# io-board-f-4.net
KiCad netlist of a schematic drawn in EAGLE
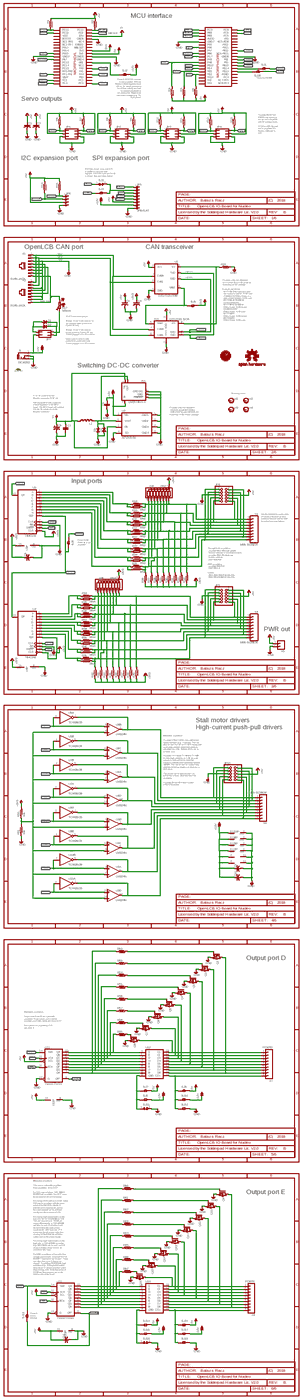
[diagram p0: schematic, sheet 1, overview]
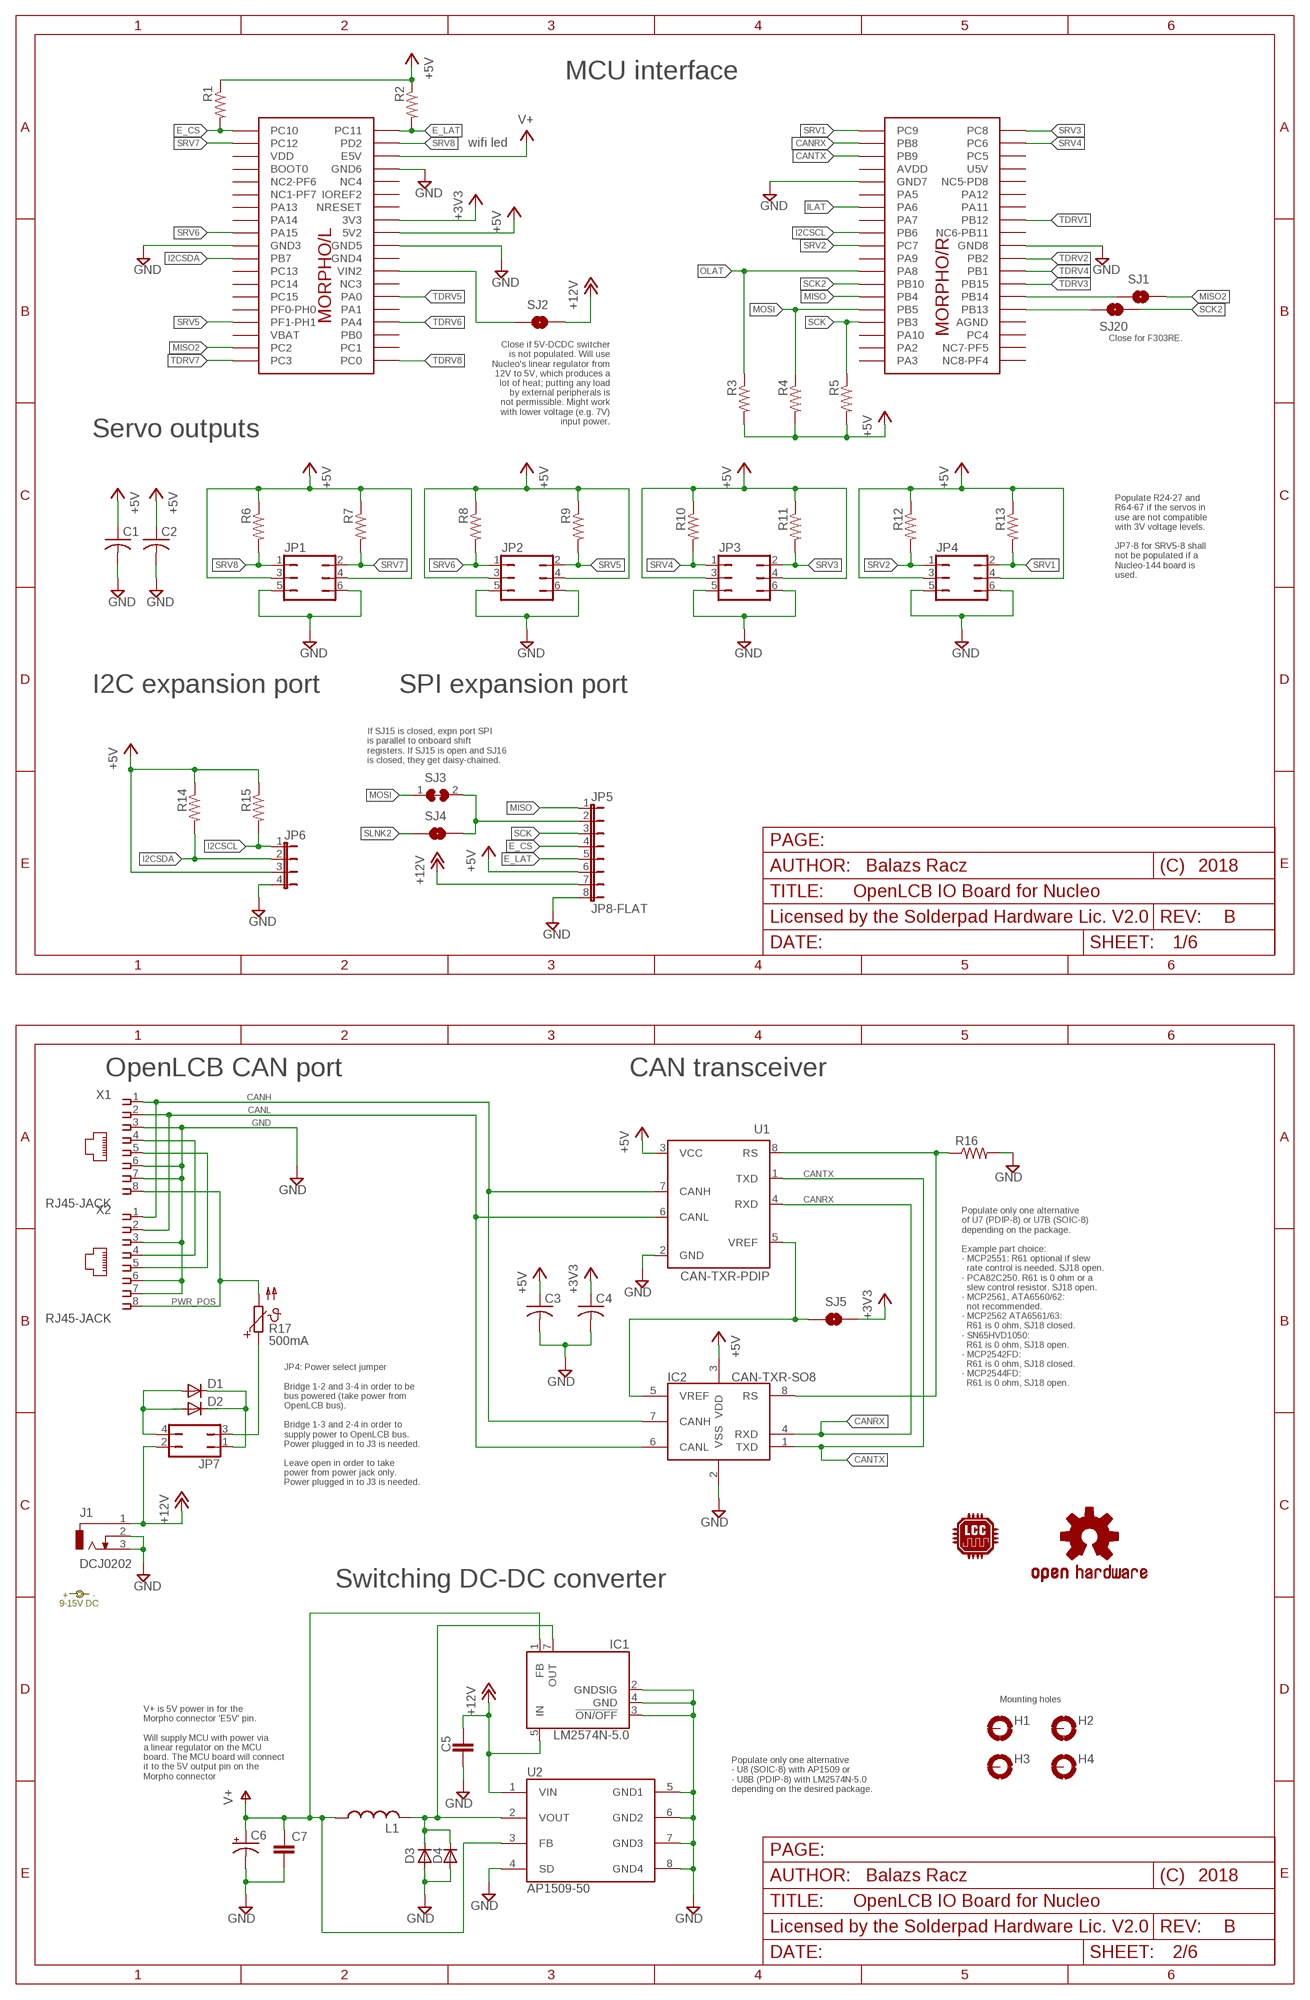
[diagram p1: schematic, sheet 1, part 1 of 4]
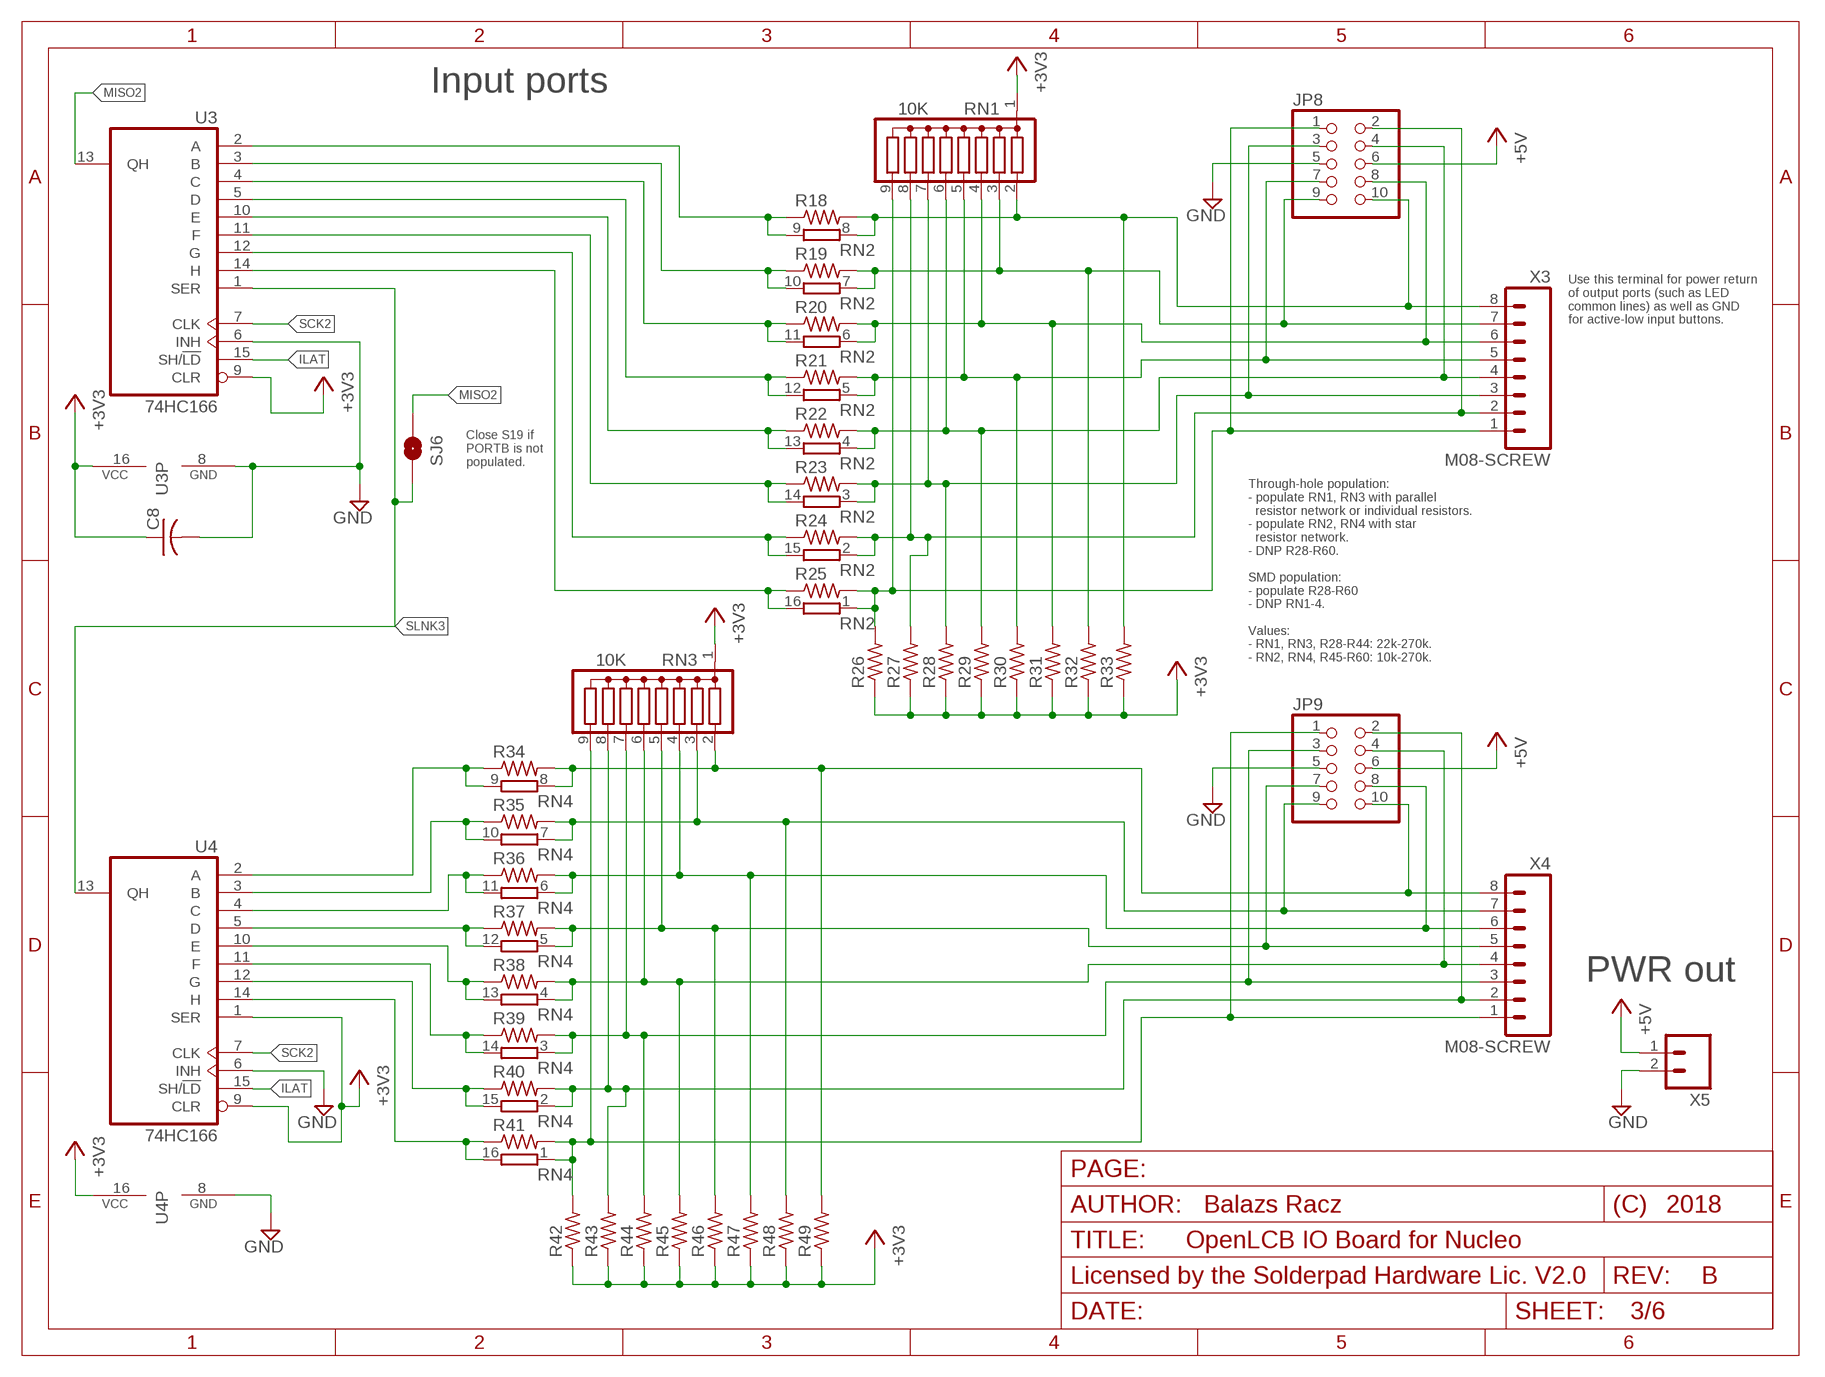
[diagram p2: schematic, sheet 1, part 2 of 4]
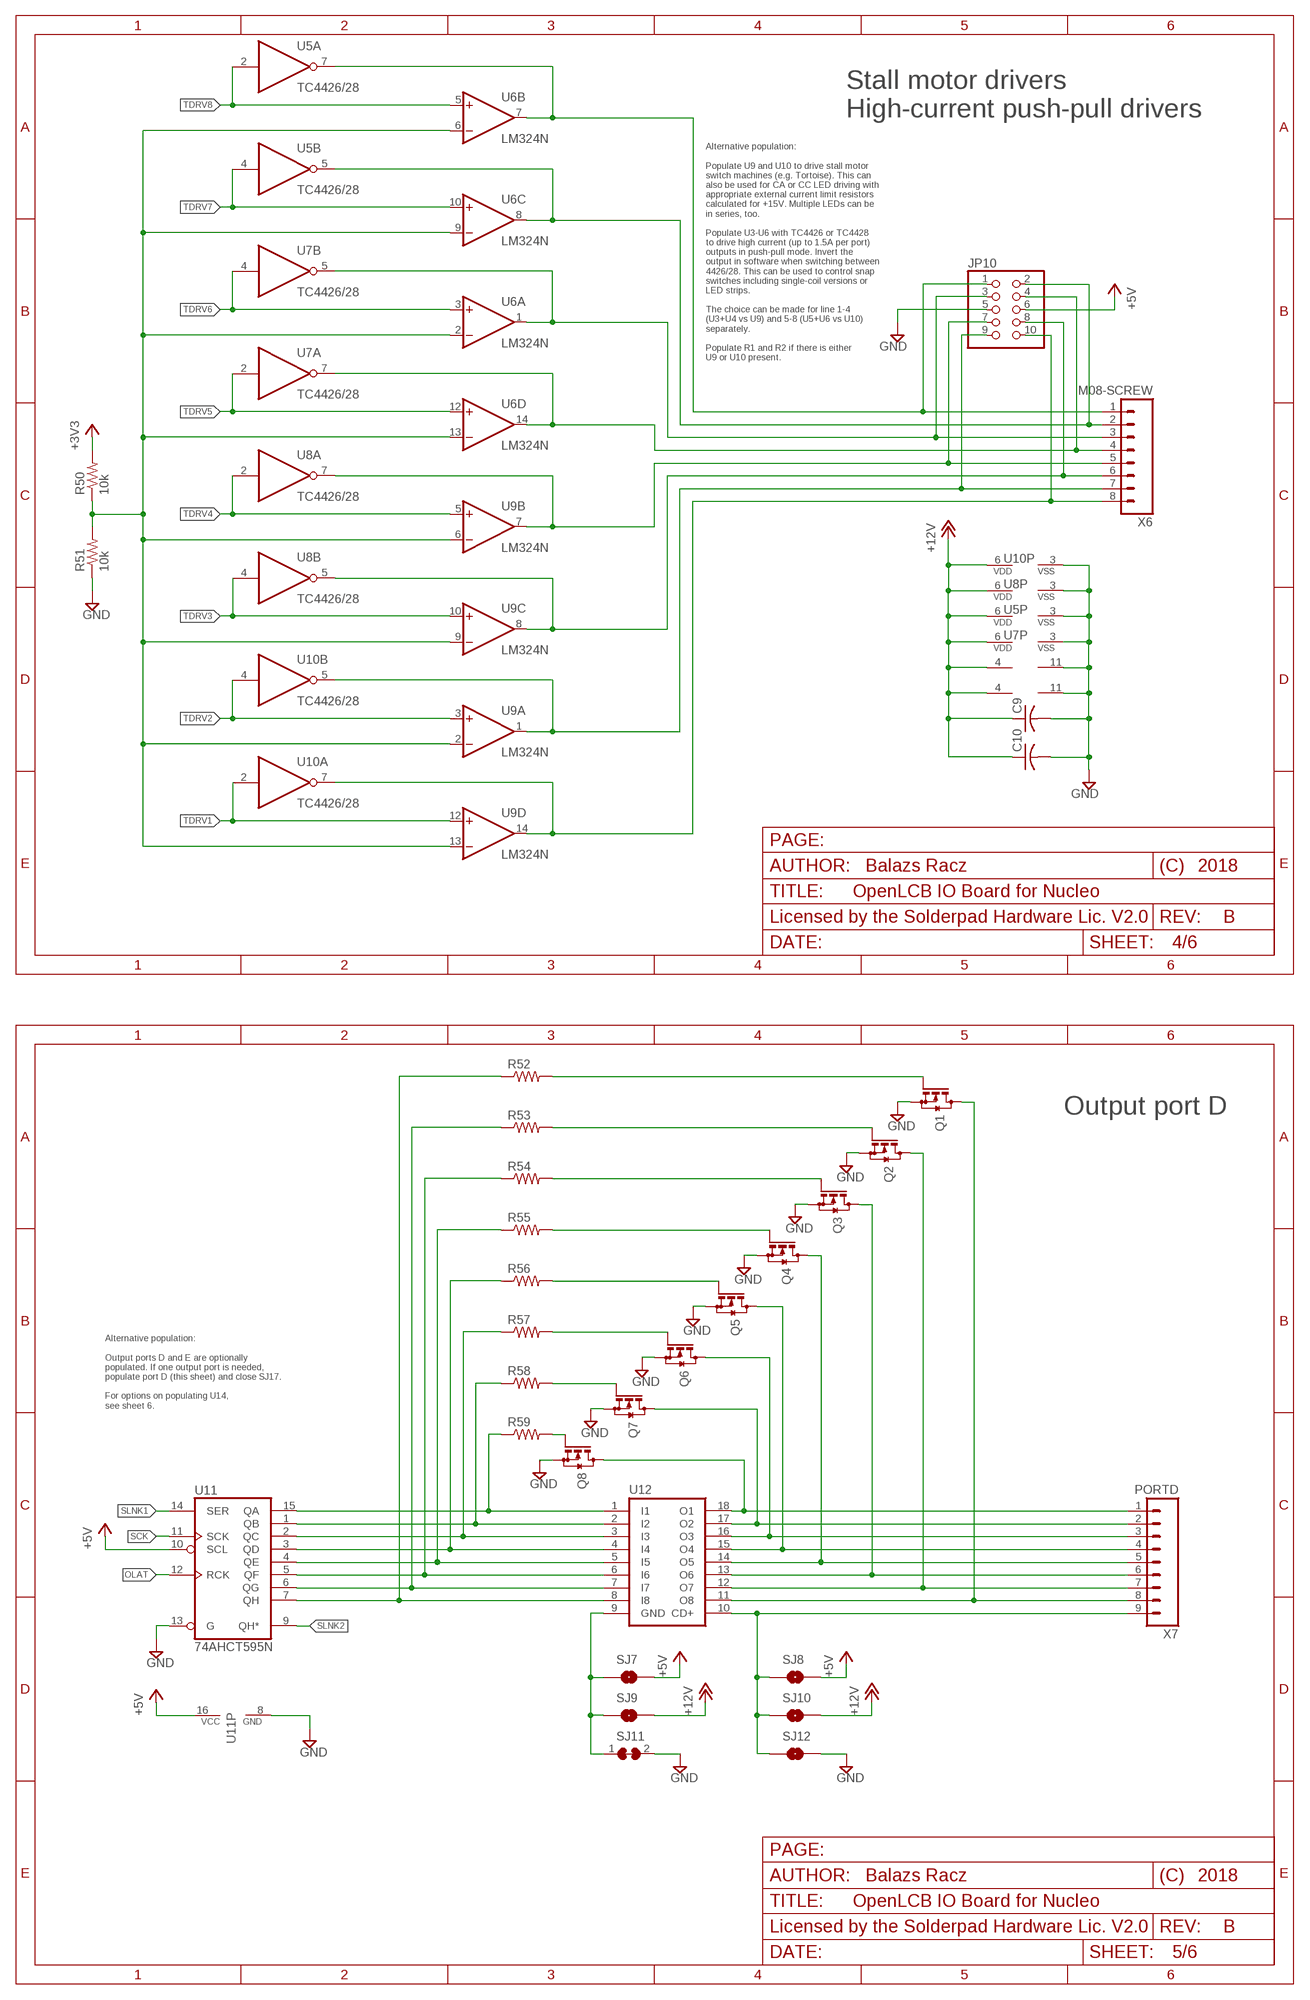
[diagram p3: schematic, sheet 1, part 3 of 4]
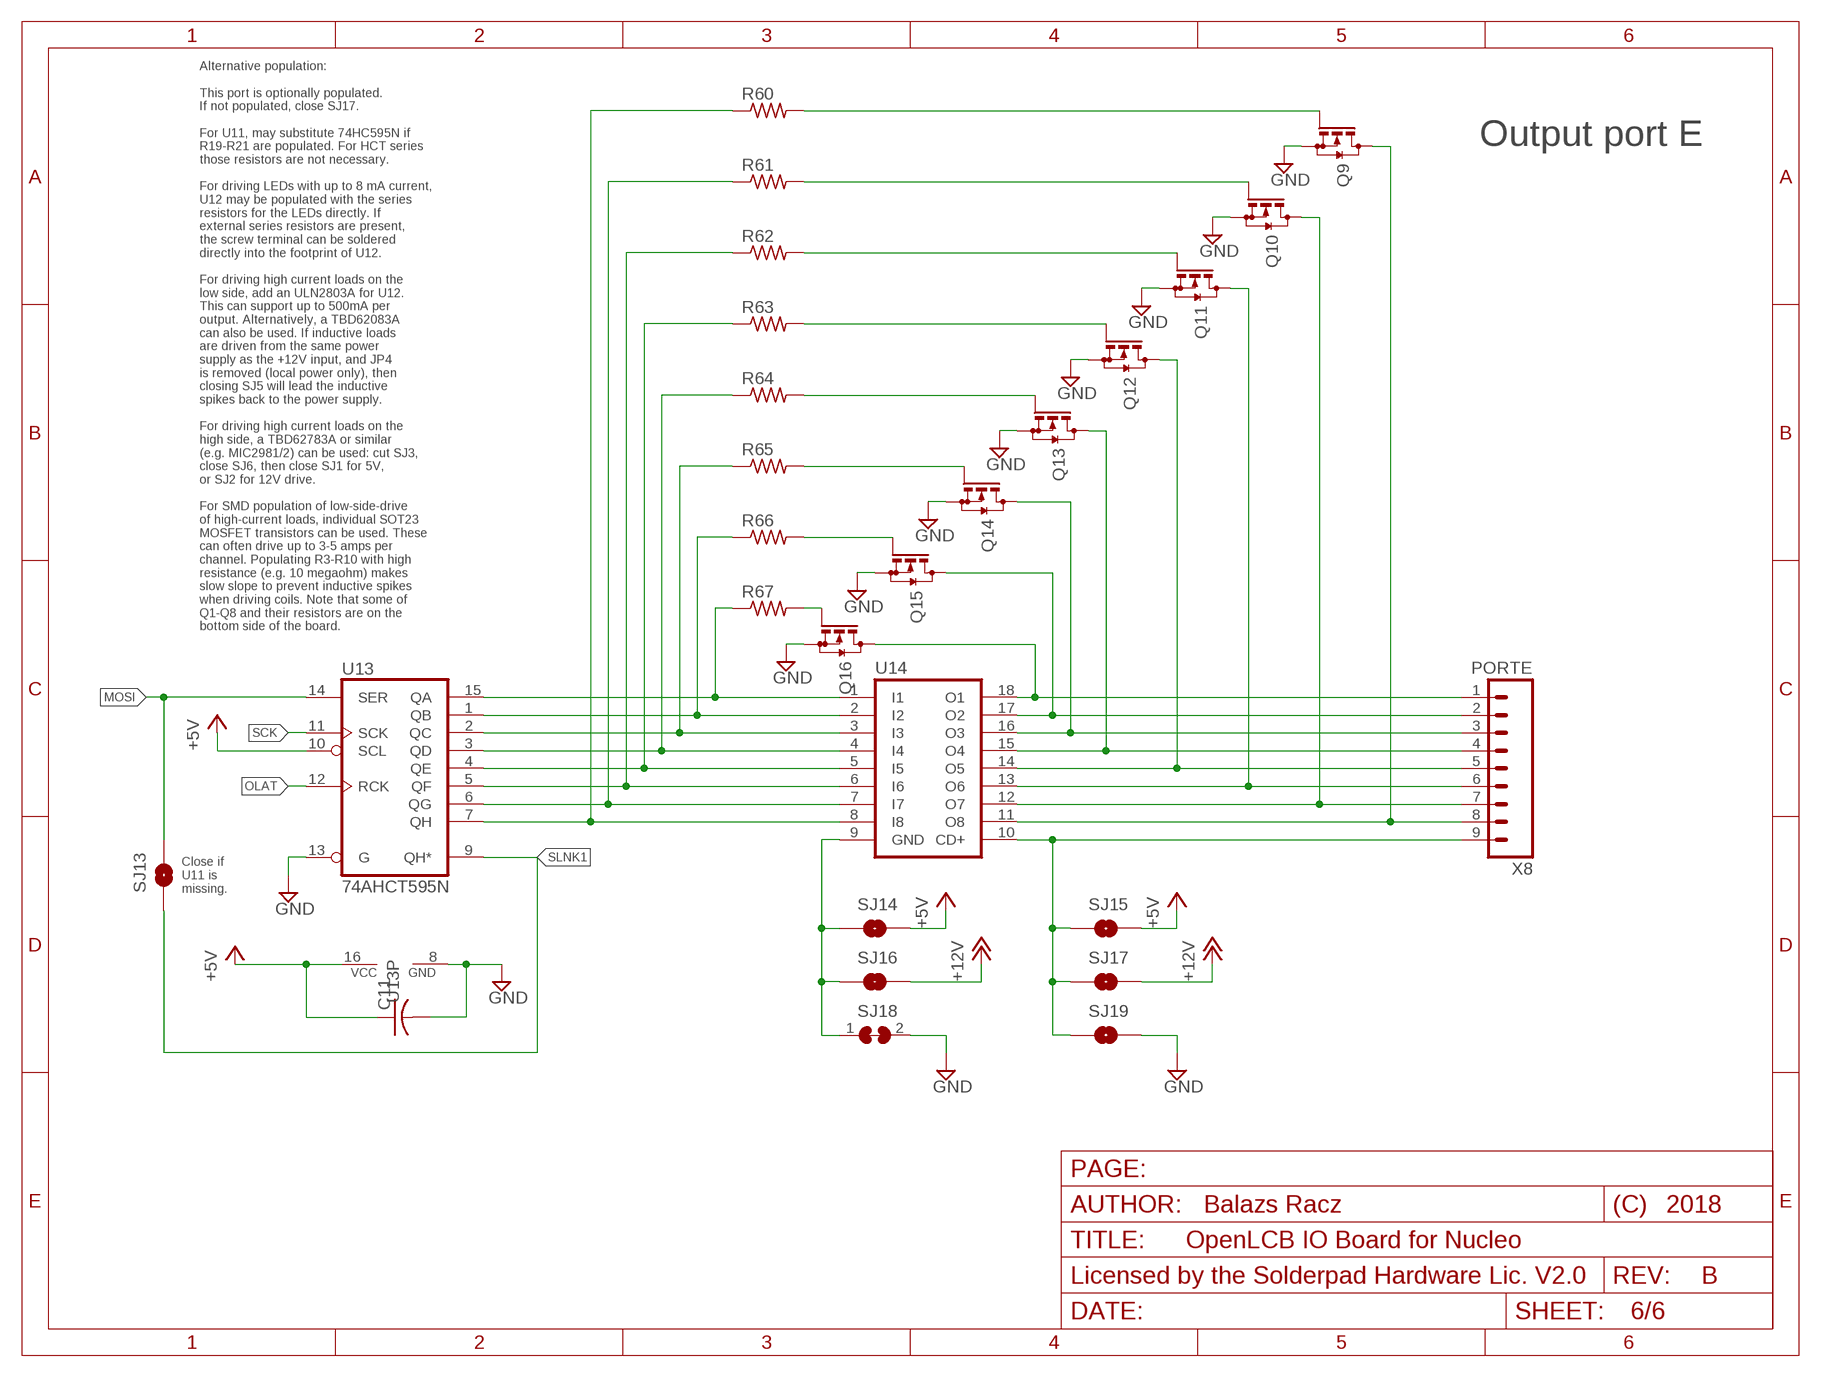
[diagram p4: schematic, sheet 1, part 4 of 4]

(export (version "E")
  (design (tool "Eeschema 10.0.6"))
  (components
    (comp (ref "C1")
      (value "C-USC1206")
      (footprint "eagle-import:C1206")
      (libsource (lib "eagle-import") (part "C-USC1206"))
    )
    (comp (ref "C2")
      (value "C-USC1206")
      (footprint "eagle-import:C1206")
      (libsource (lib "eagle-import") (part "C-USC1206"))
    )
    (comp (ref "C3")
      (value "C-USC0805")
      (footprint "eagle-import:C0805")
      (libsource (lib "eagle-import") (part "C-USC0805"))
    )
    (comp (ref "C4")
      (value "C-USC0805")
      (footprint "eagle-import:C0805")
      (libsource (lib "eagle-import") (part "C-USC0805"))
    )
    (comp (ref "C5")
      (value "C-EUC1206")
      (footprint "eagle-import:C1206")
      (libsource (lib "eagle-import") (part "C-EUC1206"))
    )
    (comp (ref "C6")
      (value "CPOL-USE2.5-5")
      (footprint "eagle-import:E2,5-5")
      (libsource (lib "eagle-import") (part "CPOL-USE2.5-5"))
    )
    (comp (ref "C7")
      (value "C-EUC1206")
      (footprint "eagle-import:C1206")
      (libsource (lib "eagle-import") (part "C-EUC1206"))
    )
    (comp (ref "C8")
      (value "C-USC0805")
      (footprint "eagle-import:C0805")
      (libsource (lib "eagle-import") (part "C-USC0805"))
    )
    (comp (ref "C9")
      (value "C-USC1206")
      (footprint "eagle-import:C1206")
      (libsource (lib "eagle-import") (part "C-USC1206"))
    )
    (comp (ref "C10")
      (value "C-USC1206")
      (footprint "eagle-import:C1206")
      (libsource (lib "eagle-import") (part "C-USC1206"))
    )
    (comp (ref "C11")
      (value "C-USC0805")
      (footprint "eagle-import:C0805")
      (libsource (lib "eagle-import") (part "C-USC0805"))
    )
    (comp (ref "D1")
      (value "DIODEDO-214AA-NODOC")
      (footprint "eagle-import:DO214AA-NODOC")
      (libsource (lib "eagle-import") (part "DIODEDO-214AA-NODOC"))
    )
    (comp (ref "D2")
      (value "DIODE-DO41-7.6")
      (footprint "eagle-import:DO41-7.6")
      (libsource (lib "eagle-import") (part "DIODE-DO41-7.6"))
    )
    (comp (ref "D3")
      (value "DIODE-DO41-7.6")
      (footprint "eagle-import:DO41-7.6")
      (libsource (lib "eagle-import") (part "DIODE-DO41-7.6"))
    )
    (comp (ref "D4")
      (value "DIODEDO-214AA-NODOC")
      (footprint "eagle-import:DO214AA-NODOC")
      (libsource (lib "eagle-import") (part "DIODEDO-214AA-NODOC"))
    )
    (comp (ref "G1")
      (value "NUCLEO_64_GENERIC")
      (footprint "eagle-import:NUCLEO_BRD_BASE64")
      (libsource (lib "eagle-import") (part "NUCLEO_64_GENERIC"))
    )
    (comp (ref "H1")
      (value "MOUNT-PAD-ROUND3.3")
      (footprint "eagle-import:3,3-PAD")
      (libsource (lib "eagle-import") (part "MOUNT-PAD-ROUND3.3"))
    )
    (comp (ref "H2")
      (value "MOUNT-PAD-ROUND3.3")
      (footprint "eagle-import:3,3-PAD")
      (libsource (lib "eagle-import") (part "MOUNT-PAD-ROUND3.3"))
    )
    (comp (ref "H3")
      (value "MOUNT-PAD-ROUND3.3")
      (footprint "eagle-import:3,3-PAD")
      (libsource (lib "eagle-import") (part "MOUNT-PAD-ROUND3.3"))
    )
    (comp (ref "H4")
      (value "MOUNT-PAD-ROUND3.3")
      (footprint "eagle-import:3,3-PAD")
      (libsource (lib "eagle-import") (part "MOUNT-PAD-ROUND3.3"))
    )
    (comp (ref "IC1")
      (value "LM2574N-5.0")
      (footprint "eagle-import:DIL08")
      (libsource (lib "eagle-import") (part "LM2574?-N5.0"))
    )
    (comp (ref "IC2")
      (value "CAN-TXR-SO8")
      (footprint "eagle-import:SO-08")
      (libsource (lib "eagle-import") (part "MCP2551-SN"))
    )
    (comp (ref "J1")
      (value "DCJ0202")
      (footprint "eagle-import:DCJ0202")
      (libsource (lib "eagle-import") (part "DCJ0202"))
    )
    (comp (ref "JP1")
      (value "JP3Q")
      (footprint "eagle-import:JP3Q")
      (libsource (lib "eagle-import") (part "JP3Q"))
    )
    (comp (ref "JP2")
      (value "JP3Q")
      (footprint "eagle-import:JP3Q")
      (libsource (lib "eagle-import") (part "JP3Q"))
    )
    (comp (ref "JP3")
      (value "JP3Q")
      (footprint "eagle-import:JP3Q")
      (libsource (lib "eagle-import") (part "JP3Q"))
    )
    (comp (ref "JP4")
      (value "JP3Q")
      (footprint "eagle-import:JP3Q")
      (libsource (lib "eagle-import") (part "JP3Q"))
    )
    (comp (ref "JP5")
      (value "JP8-FLAT")
      (footprint "eagle-import:JP8F")
      (libsource (lib "eagle-import") (part "JP8-FLAT"))
    )
    (comp (ref "JP6")
      (value "JP4-FLAT")
      (footprint "eagle-import:JP4F")
      (libsource (lib "eagle-import") (part "JP4-FLAT"))
    )
    (comp (ref "JP7")
      (value "JP2Q")
      (footprint "eagle-import:JP2Q")
      (libsource (lib "eagle-import") (part "JP2Q"))
    )
    (comp (ref "JP8")
      (value "PINHD-2X5CN")
      (footprint "eagle-import:CON10M")
      (libsource (lib "eagle-import") (part "PINHD-2X5CN"))
    )
    (comp (ref "JP9")
      (value "PINHD-2X5CN")
      (footprint "eagle-import:CON10M")
      (libsource (lib "eagle-import") (part "PINHD-2X5CN"))
    )
    (comp (ref "JP10")
      (value "PINHD-2X5CN")
      (footprint "eagle-import:CON10M")
      (libsource (lib "eagle-import") (part "PINHD-2X5CN"))
    )
    (comp (ref "L1")
      (value "L-US")
      (footprint "eagle-import:L5-8,5")
      (libsource (lib "eagle-import") (part "L-US"))
    )
    (comp (ref "LG1")
      (value "LCC_LOGO")
      (footprint "eagle-import:LCC_LOGO")
      (libsource (lib "eagle-import") (part "LCC_LOGO"))
    )
    (comp (ref "LOGO1")
      (value "DOC-OSHW-LOGOM")
      (footprint "eagle-import:OSHW-LOGO-M")
      (libsource (lib "eagle-import") (part "DOC-OSHW-LOGOM"))
    )
    (comp (ref "P1")
      (value "9-15V DC")
      (footprint "eagle-import:POWER_USAGE")
      (libsource (lib "eagle-import") (part "DOC-POWER_LABEL"))
    )
    (comp (ref "Q1")
      (value "BSS123")
      (footprint "eagle-import:SOT23")
      (libsource (lib "eagle-import") (part "BSS123"))
    )
    (comp (ref "Q2")
      (value "BSS123")
      (footprint "eagle-import:SOT23")
      (libsource (lib "eagle-import") (part "BSS123"))
    )
    (comp (ref "Q3")
      (value "BSS123")
      (footprint "eagle-import:SOT23")
      (libsource (lib "eagle-import") (part "BSS123"))
    )
    (comp (ref "Q4")
      (value "BSS123")
      (footprint "eagle-import:SOT23")
      (libsource (lib "eagle-import") (part "BSS123"))
    )
    (comp (ref "Q5")
      (value "BSS123")
      (footprint "eagle-import:SOT23")
      (libsource (lib "eagle-import") (part "BSS123"))
    )
    (comp (ref "Q6")
      (value "BSS123")
      (footprint "eagle-import:SOT23")
      (libsource (lib "eagle-import") (part "BSS123"))
    )
    (comp (ref "Q7")
      (value "BSS123")
      (footprint "eagle-import:SOT23")
      (libsource (lib "eagle-import") (part "BSS123"))
    )
    (comp (ref "Q8")
      (value "BSS123")
      (footprint "eagle-import:SOT23")
      (libsource (lib "eagle-import") (part "BSS123"))
    )
    (comp (ref "Q9")
      (value "BSS123")
      (footprint "eagle-import:SOT23")
      (libsource (lib "eagle-import") (part "BSS123"))
    )
    (comp (ref "Q10")
      (value "BSS123")
      (footprint "eagle-import:SOT23")
      (libsource (lib "eagle-import") (part "BSS123"))
    )
    (comp (ref "Q11")
      (value "BSS123")
      (footprint "eagle-import:SOT23")
      (libsource (lib "eagle-import") (part "BSS123"))
    )
    (comp (ref "Q12")
      (value "BSS123")
      (footprint "eagle-import:SOT23")
      (libsource (lib "eagle-import") (part "BSS123"))
    )
    (comp (ref "Q13")
      (value "BSS123")
      (footprint "eagle-import:SOT23")
      (libsource (lib "eagle-import") (part "BSS123"))
    )
    (comp (ref "Q14")
      (value "BSS123")
      (footprint "eagle-import:SOT23")
      (libsource (lib "eagle-import") (part "BSS123"))
    )
    (comp (ref "Q15")
      (value "BSS123")
      (footprint "eagle-import:SOT23")
      (libsource (lib "eagle-import") (part "BSS123"))
    )
    (comp (ref "Q16")
      (value "BSS123")
      (footprint "eagle-import:SOT23")
      (libsource (lib "eagle-import") (part "BSS123"))
    )
    (comp (ref "R1")
      (value "R-US_R0805")
      (footprint "eagle-import:R0805")
      (libsource (lib "eagle-import") (part "rcl_334_R-US_R0805"))
    )
    (comp (ref "R2")
      (value "R-US_R0805")
      (footprint "eagle-import:R0805")
      (libsource (lib "eagle-import") (part "rcl_334_R-US_R0805"))
    )
    (comp (ref "R3")
      (value "R-US_R0805")
      (footprint "eagle-import:R0805")
      (libsource (lib "eagle-import") (part "rcl_334_R-US_R0805"))
    )
    (comp (ref "R4")
      (value "R-US_R0805")
      (footprint "eagle-import:R0805")
      (libsource (lib "eagle-import") (part "rcl_334_R-US_R0805"))
    )
    (comp (ref "R5")
      (value "R-US_R0805")
      (footprint "eagle-import:R0805")
      (libsource (lib "eagle-import") (part "rcl_334_R-US_R0805"))
    )
    (comp (ref "R6")
      (value "R-US_R0805")
      (footprint "eagle-import:R0805")
      (libsource (lib "eagle-import") (part "rcl_334_R-US_R0805"))
    )
    (comp (ref "R7")
      (value "R-US_R0805")
      (footprint "eagle-import:R0805")
      (libsource (lib "eagle-import") (part "rcl_334_R-US_R0805"))
    )
    (comp (ref "R8")
      (value "R-US_R0805")
      (footprint "eagle-import:R0805")
      (libsource (lib "eagle-import") (part "rcl_334_R-US_R0805"))
    )
    (comp (ref "R9")
      (value "R-US_R0805")
      (footprint "eagle-import:R0805")
      (libsource (lib "eagle-import") (part "rcl_334_R-US_R0805"))
    )
    (comp (ref "R10")
      (value "R-US_R0805")
      (footprint "eagle-import:R0805")
      (libsource (lib "eagle-import") (part "rcl_334_R-US_R0805"))
    )
    (comp (ref "R11")
      (value "R-US_R0805")
      (footprint "eagle-import:R0805")
      (libsource (lib "eagle-import") (part "rcl_334_R-US_R0805"))
    )
    (comp (ref "R12")
      (value "R-US_R0805")
      (footprint "eagle-import:R0805")
      (libsource (lib "eagle-import") (part "rcl_334_R-US_R0805"))
    )
    (comp (ref "R13")
      (value "R-US_R0805")
      (footprint "eagle-import:R0805")
      (libsource (lib "eagle-import") (part "rcl_334_R-US_R0805"))
    )
    (comp (ref "R14")
      (value "R-US_R0805")
      (footprint "eagle-import:R0805")
      (libsource (lib "eagle-import") (part "rcl_334_R-US_R0805"))
    )
    (comp (ref "R15")
      (value "R-US_R0805")
      (footprint "eagle-import:R0805")
      (libsource (lib "eagle-import") (part "rcl_334_R-US_R0805"))
    )
    (comp (ref "R16")
      (value "R-US_R0805")
      (footprint "eagle-import:R0805")
      (libsource (lib "eagle-import") (part "rcl_334_R-US_R0805"))
    )
    (comp (ref "R17")
      (value "500mA")
      (footprint "eagle-import:PTC1812")
      (libsource (lib "eagle-import") (part "PTC_1812"))
    )
    (comp (ref "R18")
      (value "R-US_R0603")
      (footprint "eagle-import:R0603")
      (libsource (lib "eagle-import") (part "rcl_334_R-US_R0603"))
    )
    (comp (ref "R19")
      (value "R-US_R0603")
      (footprint "eagle-import:R0603")
      (libsource (lib "eagle-import") (part "rcl_334_R-US_R0603"))
    )
    (comp (ref "R20")
      (value "R-US_R0603")
      (footprint "eagle-import:R0603")
      (libsource (lib "eagle-import") (part "rcl_334_R-US_R0603"))
    )
    (comp (ref "R21")
      (value "R-US_R0603")
      (footprint "eagle-import:R0603")
      (libsource (lib "eagle-import") (part "rcl_334_R-US_R0603"))
    )
    (comp (ref "R22")
      (value "R-US_R0603")
      (footprint "eagle-import:R0603")
      (libsource (lib "eagle-import") (part "rcl_334_R-US_R0603"))
    )
    (comp (ref "R23")
      (value "R-US_R0603")
      (footprint "eagle-import:R0603")
      (libsource (lib "eagle-import") (part "rcl_334_R-US_R0603"))
    )
    (comp (ref "R24")
      (value "R-US_R0603")
      (footprint "eagle-import:R0603")
      (libsource (lib "eagle-import") (part "rcl_334_R-US_R0603"))
    )
    (comp (ref "R25")
      (value "R-US_R0603")
      (footprint "eagle-import:R0603")
      (libsource (lib "eagle-import") (part "rcl_334_R-US_R0603"))
    )
    (comp (ref "R26")
      (value "R-US")
      (footprint "eagle-import:R0603")
      (libsource (lib "eagle-import") (part "R-US"))
    )
    (comp (ref "R27")
      (value "R-US")
      (footprint "eagle-import:R0603")
      (libsource (lib "eagle-import") (part "R-US"))
    )
    (comp (ref "R28")
      (value "R-US")
      (footprint "eagle-import:R0603")
      (libsource (lib "eagle-import") (part "R-US"))
    )
    (comp (ref "R29")
      (value "R-US")
      (footprint "eagle-import:R0603")
      (libsource (lib "eagle-import") (part "R-US"))
    )
    (comp (ref "R30")
      (value "R-US")
      (footprint "eagle-import:R0603")
      (libsource (lib "eagle-import") (part "R-US"))
    )
    (comp (ref "R31")
      (value "R-US")
      (footprint "eagle-import:R0603")
      (libsource (lib "eagle-import") (part "R-US"))
    )
    (comp (ref "R32")
      (value "R-US")
      (footprint "eagle-import:R0603")
      (libsource (lib "eagle-import") (part "R-US"))
    )
    (comp (ref "R33")
      (value "R-US")
      (footprint "eagle-import:R0603")
      (libsource (lib "eagle-import") (part "R-US"))
    )
    (comp (ref "R34")
      (value "R-US_R0603")
      (footprint "eagle-import:R0603")
      (libsource (lib "eagle-import") (part "rcl_334_R-US_R0603"))
    )
    (comp (ref "R35")
      (value "R-US_R0603")
      (footprint "eagle-import:R0603")
      (libsource (lib "eagle-import") (part "rcl_334_R-US_R0603"))
    )
    (comp (ref "R36")
      (value "R-US_R0603")
      (footprint "eagle-import:R0603")
      (libsource (lib "eagle-import") (part "rcl_334_R-US_R0603"))
    )
    (comp (ref "R37")
      (value "R-US_R0603")
      (footprint "eagle-import:R0603")
      (libsource (lib "eagle-import") (part "rcl_334_R-US_R0603"))
    )
    (comp (ref "R38")
      (value "R-US_R0603")
      (footprint "eagle-import:R0603")
      (libsource (lib "eagle-import") (part "rcl_334_R-US_R0603"))
    )
    (comp (ref "R39")
      (value "R-US_R0603")
      (footprint "eagle-import:R0603")
      (libsource (lib "eagle-import") (part "rcl_334_R-US_R0603"))
    )
    (comp (ref "R40")
      (value "R-US_R0603")
      (footprint "eagle-import:R0603")
      (libsource (lib "eagle-import") (part "rcl_334_R-US_R0603"))
    )
    (comp (ref "R41")
      (value "R-US_R0603")
      (footprint "eagle-import:R0603")
      (libsource (lib "eagle-import") (part "rcl_334_R-US_R0603"))
    )
    (comp (ref "R42")
      (value "R-US")
      (footprint "eagle-import:R0603")
      (libsource (lib "eagle-import") (part "R-US"))
    )
    (comp (ref "R43")
      (value "R-US")
      (footprint "eagle-import:R0603")
      (libsource (lib "eagle-import") (part "R-US"))
    )
    (comp (ref "R44")
      (value "R-US")
      (footprint "eagle-import:R0603")
      (libsource (lib "eagle-import") (part "R-US"))
    )
    (comp (ref "R45")
      (value "R-US")
      (footprint "eagle-import:R0603")
      (libsource (lib "eagle-import") (part "R-US"))
    )
    (comp (ref "R46")
      (value "R-US")
      (footprint "eagle-import:R0603")
      (libsource (lib "eagle-import") (part "R-US"))
    )
    (comp (ref "R47")
      (value "R-US")
      (footprint "eagle-import:R0603")
      (libsource (lib "eagle-import") (part "R-US"))
    )
    (comp (ref "R48")
      (value "R-US")
      (footprint "eagle-import:R0603")
      (libsource (lib "eagle-import") (part "R-US"))
    )
    (comp (ref "R49")
      (value "R-US")
      (footprint "eagle-import:R0603")
      (libsource (lib "eagle-import") (part "R-US"))
    )
    (comp (ref "R50")
      (value "10k")
      (footprint "eagle-import:R0805")
      (libsource (lib "eagle-import") (part "R-US_R0805"))
    )
    (comp (ref "R51")
      (value "10k")
      (footprint "eagle-import:R0805")
      (libsource (lib "eagle-import") (part "R-US_R0805"))
    )
    (comp (ref "R52")
      (value "R-US_R0603")
      (footprint "eagle-import:R0603")
      (libsource (lib "eagle-import") (part "R-US_R0603"))
    )
    (comp (ref "R53")
      (value "R-US_R0603")
      (footprint "eagle-import:R0603")
      (libsource (lib "eagle-import") (part "R-US_R0603"))
    )
    (comp (ref "R54")
      (value "R-US_R0603")
      (footprint "eagle-import:R0603")
      (libsource (lib "eagle-import") (part "R-US_R0603"))
    )
    (comp (ref "R55")
      (value "R-US_R0603")
      (footprint "eagle-import:R0603")
      (libsource (lib "eagle-import") (part "R-US_R0603"))
    )
    (comp (ref "R56")
      (value "R-US_R0603")
      (footprint "eagle-import:R0603")
      (libsource (lib "eagle-import") (part "R-US_R0603"))
    )
    (comp (ref "R57")
      (value "R-US_R0603")
      (footprint "eagle-import:R0603")
      (libsource (lib "eagle-import") (part "R-US_R0603"))
    )
    (comp (ref "R58")
      (value "R-US_R0603")
      (footprint "eagle-import:R0603")
      (libsource (lib "eagle-import") (part "R-US_R0603"))
    )
    (comp (ref "R59")
      (value "R-US_R0603")
      (footprint "eagle-import:R0603")
      (libsource (lib "eagle-import") (part "R-US_R0603"))
    )
    (comp (ref "R60")
      (value "R-US_R0603")
      (footprint "eagle-import:R0603")
      (libsource (lib "eagle-import") (part "R-US_R0603"))
    )
    (comp (ref "R61")
      (value "R-US_R0603")
      (footprint "eagle-import:R0603")
      (libsource (lib "eagle-import") (part "R-US_R0603"))
    )
    (comp (ref "R62")
      (value "R-US_R0603")
      (footprint "eagle-import:R0603")
      (libsource (lib "eagle-import") (part "R-US_R0603"))
    )
    (comp (ref "R63")
      (value "R-US_R0603")
      (footprint "eagle-import:R0603")
      (libsource (lib "eagle-import") (part "R-US_R0603"))
    )
    (comp (ref "R64")
      (value "R-US_R0603")
      (footprint "eagle-import:R0603")
      (libsource (lib "eagle-import") (part "R-US_R0603"))
    )
    (comp (ref "R65")
      (value "R-US_R0603")
      (footprint "eagle-import:R0603")
      (libsource (lib "eagle-import") (part "R-US_R0603"))
    )
    (comp (ref "R66")
      (value "R-US_R0603")
      (footprint "eagle-import:R0603")
      (libsource (lib "eagle-import") (part "R-US_R0603"))
    )
    (comp (ref "R67")
      (value "R-US_R0603")
      (footprint "eagle-import:R0603")
      (libsource (lib "eagle-import") (part "R-US_R0603"))
    )
    (comp (ref "RN1")
      (value "10K")
      (footprint "eagle-import:SIL9")
      (libsource (lib "eagle-import") (part "G08R"))
    )
    (comp (ref "RN2")
      (value "8R-P")
      (footprint "eagle-import:DIL16")
      (libsource (lib "eagle-import") (part "8R-P"))
    )
    (comp (ref "RN3")
      (value "10K")
      (footprint "eagle-import:SIL9")
      (libsource (lib "eagle-import") (part "G08R"))
    )
    (comp (ref "RN4")
      (value "8R-P")
      (footprint "eagle-import:DIL16")
      (libsource (lib "eagle-import") (part "8R-P"))
    )
    (comp (ref "SJ1")
      (value "SJRND2")
      (footprint "eagle-import:SJ_RND2")
      (libsource (lib "eagle-import") (part "SJRND2"))
    )
    (comp (ref "SJ2")
      (value "SJRND2")
      (footprint "eagle-import:SJ_RND2")
      (libsource (lib "eagle-import") (part "SJRND2"))
    )
    (comp (ref "SJ3")
      (value "SJ-C")
      (footprint "eagle-import:SJW-C")
      (libsource (lib "eagle-import") (part "SJ-C"))
    )
    (comp (ref "SJ4")
      (value "SJRND2")
      (footprint "eagle-import:SJ_RND2")
      (libsource (lib "eagle-import") (part "SJRND2"))
    )
    (comp (ref "SJ5")
      (value "SJRND2")
      (footprint "eagle-import:SJ_RND2")
      (libsource (lib "eagle-import") (part "SJRND2"))
    )
    (comp (ref "SJ6")
      (value "SJRND2")
      (footprint "eagle-import:SJ_RND2")
      (libsource (lib "eagle-import") (part "SJRND2"))
    )
    (comp (ref "SJ7")
      (value "SJRND2")
      (footprint "eagle-import:SJ_RND2")
      (libsource (lib "eagle-import") (part "SJRND2"))
    )
    (comp (ref "SJ8")
      (value "SJRND2")
      (footprint "eagle-import:SJ_RND2")
      (libsource (lib "eagle-import") (part "SJRND2"))
    )
    (comp (ref "SJ9")
      (value "SJRND2")
      (footprint "eagle-import:SJ_RND2")
      (libsource (lib "eagle-import") (part "SJRND2"))
    )
    (comp (ref "SJ10")
      (value "SJRND2")
      (footprint "eagle-import:SJ_RND2")
      (libsource (lib "eagle-import") (part "SJRND2"))
    )
    (comp (ref "SJ11")
      (value "SJ-C")
      (footprint "eagle-import:SJW-C")
      (libsource (lib "eagle-import") (part "SJ-C"))
    )
    (comp (ref "SJ12")
      (value "SJRND2")
      (footprint "eagle-import:SJ_RND2")
      (libsource (lib "eagle-import") (part "SJRND2"))
    )
    (comp (ref "SJ13")
      (value "SJRND2")
      (footprint "eagle-import:SJ_RND2")
      (libsource (lib "eagle-import") (part "SJRND2"))
    )
    (comp (ref "SJ14")
      (value "SJRND2")
      (footprint "eagle-import:SJ_RND2")
      (libsource (lib "eagle-import") (part "SJRND2"))
    )
    (comp (ref "SJ15")
      (value "SJRND2")
      (footprint "eagle-import:SJ_RND2")
      (libsource (lib "eagle-import") (part "SJRND2"))
    )
    (comp (ref "SJ16")
      (value "SJRND2")
      (footprint "eagle-import:SJ_RND2")
      (libsource (lib "eagle-import") (part "SJRND2"))
    )
    (comp (ref "SJ17")
      (value "SJRND2")
      (footprint "eagle-import:SJ_RND2")
      (libsource (lib "eagle-import") (part "SJRND2"))
    )
    (comp (ref "SJ18")
      (value "SJ-C")
      (footprint "eagle-import:SJW-C")
      (libsource (lib "eagle-import") (part "SJ-C"))
    )
    (comp (ref "SJ19")
      (value "SJRND2")
      (footprint "eagle-import:SJ_RND2")
      (libsource (lib "eagle-import") (part "SJRND2"))
    )
    (comp (ref "SJ20")
      (value "SJRND2")
      (footprint "eagle-import:SJ_RND2")
      (libsource (lib "eagle-import") (part "SJRND2"))
    )
    (comp (ref "U1")
      (value "CAN-TXR-PDIP")
      (footprint "eagle-import:DIL08")
      (libsource (lib "eagle-import") (part "PCA82C250"))
    )
    (comp (ref "U2")
      (value "AP1509-50")
      (footprint "eagle-import:SO-08")
      (libsource (lib "eagle-import") (part "AP1509"))
    )
    (comp (ref "U3")
      (value "74HC166")
      (footprint "eagle-import:DIL16")
      (libsource (lib "eagle-import") (part "74166N"))
    )
    (comp (ref "U4")
      (value "74HC166")
      (footprint "eagle-import:DIL16")
      (libsource (lib "eagle-import") (part "74166N"))
    )
    (comp (ref "U5")
      (value "TC4426/28")
      (footprint "eagle-import:DIL08-LONG")
      (libsource (lib "eagle-import") (part "TC4426APDIP"))
    )
    (comp (ref "U6")
      (value "LM324N")
      (footprint "eagle-import:DIL14")
      (libsource (lib "eagle-import") (part "LM324N"))
    )
    (comp (ref "U7")
      (value "TC4426/28")
      (footprint "eagle-import:DIL08-LONG")
      (libsource (lib "eagle-import") (part "TC4426APDIP"))
    )
    (comp (ref "U8")
      (value "TC4426/28")
      (footprint "eagle-import:DIL08-LONG")
      (libsource (lib "eagle-import") (part "TC4426APDIP"))
    )
    (comp (ref "U9")
      (value "LM324N")
      (footprint "eagle-import:DIL14")
      (libsource (lib "eagle-import") (part "LM324N"))
    )
    (comp (ref "U10")
      (value "TC4426/28")
      (footprint "eagle-import:DIL08-LONG")
      (libsource (lib "eagle-import") (part "TC4426APDIP"))
    )
    (comp (ref "U11")
      (value "74AHCT595N")
      (footprint "eagle-import:DIL16")
      (libsource (lib "eagle-import") (part "74595NHCT"))
    )
    (comp (ref "U12")
      (value "ULN2803A")
      (footprint "eagle-import:DIL18-THIN")
      (libsource (lib "eagle-import") (part "ULN2803A"))
    )
    (comp (ref "U13")
      (value "74AHCT595N")
      (footprint "eagle-import:DIL16")
      (libsource (lib "eagle-import") (part "74595NHCT"))
    )
    (comp (ref "U14")
      (value "ULN2803A")
      (footprint "eagle-import:DIL18-THIN")
      (libsource (lib "eagle-import") (part "ULN2803A"))
    )
    (comp (ref "X1")
      (value "RJ45-JACK")
      (footprint "eagle-import:RJ45-PULSE-E5J88")
      (libsource (lib "eagle-import") (part "RJ45-JACKRJ45-PULSE-E5J00"))
    )
    (comp (ref "X2")
      (value "RJ45-JACK")
      (footprint "eagle-import:RJ45-PULSE-E5J88")
      (libsource (lib "eagle-import") (part "RJ45-JACKRJ45-PULSE-E5J00"))
    )
    (comp (ref "X3")
      (value "M08-SCREW")
      (footprint "eagle-import:1X08_TERMINAL")
      (libsource (lib "eagle-import") (part "M08-SCREW"))
    )
    (comp (ref "X4")
      (value "M08-SCREW")
      (footprint "eagle-import:1X08_TERMINAL")
      (libsource (lib "eagle-import") (part "M08-SCREW"))
    )
    (comp (ref "X5")
      (value "CONNECTOR-M023.5MM-LOCK")
      (footprint "eagle-import:SCREWTERMINAL-3.5MM-2_LOCK")
      (libsource (lib "eagle-import") (part "CONNECTOR-M023.5MM-LOCK"))
    )
    (comp (ref "X6")
      (value "M08-SCREW")
      (footprint "eagle-import:1X08_TERMINAL")
      (libsource (lib "eagle-import") (part "M08-SCREW"))
    )
    (comp (ref "X7")
      (value "PORTD")
      (footprint "eagle-import:1X09_TERMINAL")
      (libsource (lib "eagle-import") (part "M09-SCREW"))
    )
    (comp (ref "X8")
      (value "PORTE")
      (footprint "eagle-import:1X09_TERMINAL")
      (libsource (lib "eagle-import") (part "M09-SCREW"))
    )
  )
  (nets
    (net (code "1") (name "+3V3") (class "Default")
      (node (ref "C4") (pin "1") (pinfunction "1_1") (pintype "passive"))
      (node (ref "C8") (pin "1") (pinfunction "1_1") (pintype "passive"))
      (node (ref "G1") (pin "3V3") (pinfunction "3V3_3V3") (pintype "power_in"))
      (node (ref "R26") (pin "1") (pinfunction "1_1") (pintype "passive"))
      (node (ref "R27") (pin "1") (pinfunction "1_1") (pintype "passive"))
      (node (ref "R28") (pin "1") (pinfunction "1_1") (pintype "passive"))
      (node (ref "R29") (pin "1") (pinfunction "1_1") (pintype "passive"))
      (node (ref "R30") (pin "1") (pinfunction "1_1") (pintype "passive"))
      (node (ref "R31") (pin "1") (pinfunction "1_1") (pintype "passive"))
      (node (ref "R32") (pin "1") (pinfunction "1_1") (pintype "passive"))
      (node (ref "R33") (pin "1") (pinfunction "1_1") (pintype "passive"))
      (node (ref "R42") (pin "1") (pinfunction "1_1") (pintype "passive"))
      (node (ref "R43") (pin "1") (pinfunction "1_1") (pintype "passive"))
      (node (ref "R44") (pin "1") (pinfunction "1_1") (pintype "passive"))
      (node (ref "R45") (pin "1") (pinfunction "1_1") (pintype "passive"))
      (node (ref "R46") (pin "1") (pinfunction "1_1") (pintype "passive"))
      (node (ref "R47") (pin "1") (pinfunction "1_1") (pintype "passive"))
      (node (ref "R48") (pin "1") (pinfunction "1_1") (pintype "passive"))
      (node (ref "R49") (pin "1") (pinfunction "1_1") (pintype "passive"))
      (node (ref "R50") (pin "2") (pinfunction "2_2") (pintype "passive"))
      (node (ref "RN1") (pin "1") (pinfunction "1_1") (pintype "passive"))
      (node (ref "RN3") (pin "1") (pinfunction "1_1") (pintype "passive"))
      (node (ref "SJ5") (pin "P$1") (pinfunction "1_P$1") (pintype "passive"))
      (node (ref "U3") (pin "16") (pinfunction "VCC_16") (pintype "power_in"))
      (node (ref "U3") (pin "9") (pinfunction "CLR_9") (pintype "input"))
      (node (ref "U4") (pin "1") (pinfunction "SER_1") (pintype "input"))
      (node (ref "U4") (pin "16") (pinfunction "VCC_16") (pintype "power_in"))
      (node (ref "U4") (pin "9") (pinfunction "CLR_9") (pintype "input"))
    )
    (net (code "2") (name "+5V") (class "Default")
      (node (ref "C1") (pin "1") (pinfunction "1_1") (pintype "passive"))
      (node (ref "C11") (pin "1") (pinfunction "1_1") (pintype "passive"))
      (node (ref "C2") (pin "1") (pinfunction "1_1") (pintype "passive"))
      (node (ref "C3") (pin "1") (pinfunction "1_1") (pintype "passive"))
      (node (ref "G1") (pin "5V2") (pinfunction "5V2_5V2") (pintype "power_in"))
      (node (ref "IC2") (pin "3") (pinfunction "VDD_3") (pintype "power_in"))
      (node (ref "JP1") (pin "3") (pinfunction "3_3") (pintype "passive"))
      (node (ref "JP1") (pin "4") (pinfunction "4_4") (pintype "passive"))
      (node (ref "JP10") (pin "6") (pinfunction "6_6") (pintype "passive"))
      (node (ref "JP2") (pin "3") (pinfunction "3_3") (pintype "passive"))
      (node (ref "JP2") (pin "4") (pinfunction "4_4") (pintype "passive"))
      (node (ref "JP3") (pin "3") (pinfunction "3_3") (pintype "passive"))
      (node (ref "JP3") (pin "4") (pinfunction "4_4") (pintype "passive"))
      (node (ref "JP4") (pin "3") (pinfunction "3_3") (pintype "passive"))
      (node (ref "JP4") (pin "4") (pinfunction "4_4") (pintype "passive"))
      (node (ref "JP5") (pin "6") (pinfunction "6_6") (pintype "passive"))
      (node (ref "JP6") (pin "3") (pinfunction "3_3") (pintype "passive"))
      (node (ref "JP8") (pin "6") (pinfunction "6_6") (pintype "passive"))
      (node (ref "JP9") (pin "6") (pinfunction "6_6") (pintype "passive"))
      (node (ref "R1") (pin "1") (pinfunction "1_1") (pintype "passive"))
      (node (ref "R10") (pin "1") (pinfunction "1_1") (pintype "passive"))
      (node (ref "R11") (pin "1") (pinfunction "1_1") (pintype "passive"))
      (node (ref "R12") (pin "1") (pinfunction "1_1") (pintype "passive"))
      (node (ref "R13") (pin "1") (pinfunction "1_1") (pintype "passive"))
      (node (ref "R14") (pin "1") (pinfunction "1_1") (pintype "passive"))
      (node (ref "R15") (pin "1") (pinfunction "1_1") (pintype "passive"))
      (node (ref "R2") (pin "1") (pinfunction "1_1") (pintype "passive"))
      (node (ref "R3") (pin "2") (pinfunction "2_2") (pintype "passive"))
      (node (ref "R4") (pin "2") (pinfunction "2_2") (pintype "passive"))
      (node (ref "R5") (pin "2") (pinfunction "2_2") (pintype "passive"))
      (node (ref "R6") (pin "1") (pinfunction "1_1") (pintype "passive"))
      (node (ref "R7") (pin "1") (pinfunction "1_1") (pintype "passive"))
      (node (ref "R8") (pin "1") (pinfunction "1_1") (pintype "passive"))
      (node (ref "R9") (pin "1") (pinfunction "1_1") (pintype "passive"))
      (node (ref "SJ14") (pin "P$2") (pinfunction "2_P$2") (pintype "passive"))
      (node (ref "SJ15") (pin "P$2") (pinfunction "2_P$2") (pintype "passive"))
      (node (ref "SJ7") (pin "P$2") (pinfunction "2_P$2") (pintype "passive"))
      (node (ref "SJ8") (pin "P$2") (pinfunction "2_P$2") (pintype "passive"))
      (node (ref "U1") (pin "3") (pinfunction "VCC_3") (pintype "power_in"))
      (node (ref "U11") (pin "10") (pinfunction "SCL_10") (pintype "input"))
      (node (ref "U11") (pin "16") (pinfunction "VCC_16") (pintype "power_in"))
      (node (ref "U13") (pin "10") (pinfunction "SCL_10") (pintype "input"))
      (node (ref "U13") (pin "16") (pinfunction "VCC_16") (pintype "power_in"))
      (node (ref "X5") (pin "1") (pinfunction "1_1") (pintype "passive"))
    )
    (net (code "3") (name "+12V") (class "Default")
      (node (ref "C10") (pin "1") (pinfunction "1_1") (pintype "passive"))
      (node (ref "C5") (pin "1") (pinfunction "1_1") (pintype "passive"))
      (node (ref "C9") (pin "1") (pinfunction "1_1") (pintype "passive"))
      (node (ref "IC1") (pin "5") (pinfunction "IN_5") (pintype "input"))
      (node (ref "J1") (pin "1") (pinfunction "1_1") (pintype "passive"))
      (node (ref "JP5") (pin "7") (pinfunction "7_7") (pintype "passive"))
      (node (ref "JP7") (pin "2") (pinfunction "2_2") (pintype "passive"))
      (node (ref "SJ10") (pin "P$2") (pinfunction "2_P$2") (pintype "passive"))
      (node (ref "SJ16") (pin "P$2") (pinfunction "2_P$2") (pintype "passive"))
      (node (ref "SJ17") (pin "P$2") (pinfunction "2_P$2") (pintype "passive"))
      (node (ref "SJ2") (pin "P$2") (pinfunction "2_P$2") (pintype "passive"))
      (node (ref "SJ9") (pin "P$2") (pinfunction "2_P$2") (pintype "passive"))
      (node (ref "U10") (pin "6") (pinfunction "VDD_6") (pintype "power_in"))
      (node (ref "U2") (pin "1") (pinfunction "VIN_1") (pintype "bidirectional"))
      (node (ref "U5") (pin "6") (pinfunction "VDD_6") (pintype "power_in"))
      (node (ref "U6") (pin "4") (pinfunction "V+_4") (pintype "power_in"))
      (node (ref "U7") (pin "6") (pinfunction "VDD_6") (pintype "power_in"))
      (node (ref "U8") (pin "6") (pinfunction "VDD_6") (pintype "power_in"))
      (node (ref "U9") (pin "4") (pinfunction "V+_4") (pintype "power_in"))
    )
    (net (code "4") (name "/AGND") (class "Default")
      (node (ref "G1") (pin "AGND") (pinfunction "AGND_AGND") (pintype "power_in"))
    )
    (net (code "5") (name "/AVDD") (class "Default")
      (node (ref "G1") (pin "AVDD") (pinfunction "AVDD_AVDD") (pintype "power_in"))
    )
    (net (code "6") (name "/CANH") (class "Default")
      (node (ref "IC2") (pin "7") (pinfunction "CANH_7") (pintype "bidirectional"))
      (node (ref "U1") (pin "7") (pinfunction "CANH_7") (pintype "bidirectional"))
      (node (ref "X1") (pin "1") (pinfunction "1_1") (pintype "passive"))
      (node (ref "X2") (pin "1") (pinfunction "1_1") (pintype "passive"))
    )
    (net (code "7") (name "/CANL") (class "Default")
      (node (ref "IC2") (pin "6") (pinfunction "CANL_6") (pintype "bidirectional"))
      (node (ref "U1") (pin "6") (pinfunction "CANL_6") (pintype "bidirectional"))
      (node (ref "X1") (pin "2") (pinfunction "2_2") (pintype "passive"))
      (node (ref "X2") (pin "2") (pinfunction "2_2") (pintype "passive"))
    )
    (net (code "8") (name "/GND4") (class "Default")
      (node (ref "G1") (pin "GND4") (pinfunction "GND4_GND4") (pintype "power_in"))
    )
    (net (code "9") (name "/PWR_POS") (class "Default")
      (node (ref "R17") (pin "2") (pinfunction "2_2") (pintype "passive"))
      (node (ref "X1") (pin "8") (pinfunction "8_8") (pintype "passive"))
      (node (ref "X2") (pin "8") (pinfunction "8_8") (pintype "passive"))
    )
    (net (code "10") (name "/U5V") (class "Default")
      (node (ref "G1") (pin "U5V") (pinfunction "U5V_U5V") (pintype "power_in"))
    )
    (net (code "11") (name "/VBAT") (class "Default")
      (node (ref "G1") (pin "VBAT") (pinfunction "VBAT_VBAT") (pintype "power_in"))
    )
    (net (code "12") (name "/VDD") (class "Default")
      (node (ref "G1") (pin "VDD") (pinfunction "VDD_VDD") (pintype "power_in"))
    )
    (net (code "13") (name "CANRX") (class "Default")
      (node (ref "G1") (pin "PB8") (pinfunction "PB8_PB8") (pintype "bidirectional"))
      (node (ref "IC2") (pin "4") (pinfunction "RXD_4") (pintype "bidirectional"))
      (node (ref "U1") (pin "4") (pinfunction "RXD_4") (pintype "output"))
    )
    (net (code "14") (name "CANTX") (class "Default")
      (node (ref "G1") (pin "PB9") (pinfunction "PB9_PB9") (pintype "bidirectional"))
      (node (ref "IC2") (pin "1") (pinfunction "TXD_1") (pintype "bidirectional"))
      (node (ref "U1") (pin "1") (pinfunction "TXD_1") (pintype "input"))
    )
    (net (code "15") (name "E_CS") (class "Default")
      (node (ref "G1") (pin "PC10") (pinfunction "PC10_PC10") (pintype "bidirectional"))
      (node (ref "JP5") (pin "4") (pinfunction "4_4") (pintype "passive"))
      (node (ref "R1") (pin "2") (pinfunction "2_2") (pintype "passive"))
    )
    (net (code "16") (name "E_LAT") (class "Default")
      (node (ref "G1") (pin "PC11") (pinfunction "PC11_PC11") (pintype "bidirectional"))
      (node (ref "JP5") (pin "5") (pinfunction "5_5") (pintype "passive"))
      (node (ref "R2") (pin "2") (pinfunction "2_2") (pintype "passive"))
    )
    (net (code "17") (name "GND") (class "Default")
      (node (ref "C1") (pin "2") (pinfunction "2_2") (pintype "passive"))
      (node (ref "C10") (pin "2") (pinfunction "2_2") (pintype "passive"))
      (node (ref "C11") (pin "2") (pinfunction "2_2") (pintype "passive"))
      (node (ref "C2") (pin "2") (pinfunction "2_2") (pintype "passive"))
      (node (ref "C3") (pin "2") (pinfunction "2_2") (pintype "passive"))
      (node (ref "C4") (pin "2") (pinfunction "2_2") (pintype "passive"))
      (node (ref "C5") (pin "2") (pinfunction "2_2") (pintype "passive"))
      (node (ref "C6") (pin "-") (pinfunction "-_-") (pintype "passive"))
      (node (ref "C7") (pin "2") (pinfunction "2_2") (pintype "passive"))
      (node (ref "C8") (pin "2") (pinfunction "2_2") (pintype "passive"))
      (node (ref "C9") (pin "2") (pinfunction "2_2") (pintype "passive"))
      (node (ref "D3") (pin "A") (pinfunction "A_A") (pintype "passive"))
      (node (ref "D4") (pin "A") (pinfunction "A_A") (pintype "passive"))
      (node (ref "G1") (pin "GND3") (pinfunction "GND3_GND3") (pintype "power_in"))
      (node (ref "G1") (pin "GND5") (pinfunction "GND5_GND5") (pintype "power_in"))
      (node (ref "G1") (pin "GND6") (pinfunction "GND6_GND6") (pintype "power_in"))
      (node (ref "G1") (pin "GND7") (pinfunction "GND7_GND7") (pintype "power_in"))
      (node (ref "G1") (pin "GND8") (pinfunction "GND8_GND8") (pintype "power_in"))
      (node (ref "IC1") (pin "2") (pinfunction "GNDSIG_2") (pintype "input"))
      (node (ref "IC1") (pin "3") (pinfunction "~{ON/OFF}_3") (pintype "input"))
      (node (ref "IC1") (pin "4") (pinfunction "GND_4") (pintype "power_in"))
      (node (ref "IC2") (pin "2") (pinfunction "VSS_2") (pintype "power_in"))
      (node (ref "J1") (pin "2") (pinfunction "2_2") (pintype "passive"))
      (node (ref "J1") (pin "3") (pinfunction "3_3") (pintype "passive"))
      (node (ref "JP1") (pin "5") (pinfunction "5_5") (pintype "passive"))
      (node (ref "JP1") (pin "6") (pinfunction "6_6") (pintype "passive"))
      (node (ref "JP10") (pin "5") (pinfunction "5_5") (pintype "passive"))
      (node (ref "JP2") (pin "5") (pinfunction "5_5") (pintype "passive"))
      (node (ref "JP2") (pin "6") (pinfunction "6_6") (pintype "passive"))
      (node (ref "JP3") (pin "5") (pinfunction "5_5") (pintype "passive"))
      (node (ref "JP3") (pin "6") (pinfunction "6_6") (pintype "passive"))
      (node (ref "JP4") (pin "5") (pinfunction "5_5") (pintype "passive"))
      (node (ref "JP4") (pin "6") (pinfunction "6_6") (pintype "passive"))
      (node (ref "JP5") (pin "8") (pinfunction "8_8") (pintype "passive"))
      (node (ref "JP6") (pin "4") (pinfunction "4_4") (pintype "passive"))
      (node (ref "JP8") (pin "5") (pinfunction "5_5") (pintype "passive"))
      (node (ref "JP9") (pin "5") (pinfunction "5_5") (pintype "passive"))
      (node (ref "Q1") (pin "2") (pinfunction "S_2") (pintype "passive"))
      (node (ref "Q10") (pin "2") (pinfunction "S_2") (pintype "passive"))
      (node (ref "Q11") (pin "2") (pinfunction "S_2") (pintype "passive"))
      (node (ref "Q12") (pin "2") (pinfunction "S_2") (pintype "passive"))
      (node (ref "Q13") (pin "2") (pinfunction "S_2") (pintype "passive"))
      (node (ref "Q14") (pin "2") (pinfunction "S_2") (pintype "passive"))
      (node (ref "Q15") (pin "2") (pinfunction "S_2") (pintype "passive"))
      (node (ref "Q16") (pin "2") (pinfunction "S_2") (pintype "passive"))
      (node (ref "Q2") (pin "2") (pinfunction "S_2") (pintype "passive"))
      (node (ref "Q3") (pin "2") (pinfunction "S_2") (pintype "passive"))
      (node (ref "Q4") (pin "2") (pinfunction "S_2") (pintype "passive"))
      (node (ref "Q5") (pin "2") (pinfunction "S_2") (pintype "passive"))
      (node (ref "Q6") (pin "2") (pinfunction "S_2") (pintype "passive"))
      (node (ref "Q7") (pin "2") (pinfunction "S_2") (pintype "passive"))
      (node (ref "Q8") (pin "2") (pinfunction "S_2") (pintype "passive"))
      (node (ref "Q9") (pin "2") (pinfunction "S_2") (pintype "passive"))
      (node (ref "R16") (pin "2") (pinfunction "2_2") (pintype "passive"))
      (node (ref "R51") (pin "1") (pinfunction "1_1") (pintype "passive"))
      (node (ref "SJ11") (pin "2") (pinfunction "2_2") (pintype "passive"))
      (node (ref "SJ12") (pin "P$2") (pinfunction "2_P$2") (pintype "passive"))
      (node (ref "SJ18") (pin "2") (pinfunction "2_2") (pintype "passive"))
      (node (ref "SJ19") (pin "P$2") (pinfunction "2_P$2") (pintype "passive"))
      (node (ref "U1") (pin "2") (pinfunction "GND_2") (pintype "power_in"))
      (node (ref "U10") (pin "3") (pinfunction "VSS_3") (pintype "power_in"))
      (node (ref "U11") (pin "13") (pinfunction "G_13") (pintype "input"))
      (node (ref "U11") (pin "8") (pinfunction "GND_8") (pintype "power_in"))
      (node (ref "U13") (pin "13") (pinfunction "G_13") (pintype "input"))
      (node (ref "U13") (pin "8") (pinfunction "GND_8") (pintype "power_in"))
      (node (ref "U2") (pin "4") (pinfunction "SD_4") (pintype "bidirectional"))
      (node (ref "U2") (pin "5") (pinfunction "GND1_5") (pintype "power_in"))
      (node (ref "U2") (pin "6") (pinfunction "GND2_6") (pintype "power_in"))
      (node (ref "U2") (pin "7") (pinfunction "GND3_7") (pintype "power_in"))
      (node (ref "U2") (pin "8") (pinfunction "GND4_8") (pintype "power_in"))
      (node (ref "U3") (pin "6") (pinfunction "INH_6") (pintype "input"))
      (node (ref "U3") (pin "8") (pinfunction "GND_8") (pintype "power_in"))
      (node (ref "U4") (pin "6") (pinfunction "INH_6") (pintype "input"))
      (node (ref "U4") (pin "8") (pinfunction "GND_8") (pintype "power_in"))
      (node (ref "U5") (pin "3") (pinfunction "VSS_3") (pintype "power_in"))
      (node (ref "U6") (pin "11") (pinfunction "V-_11") (pintype "power_in"))
      (node (ref "U7") (pin "3") (pinfunction "VSS_3") (pintype "power_in"))
      (node (ref "U8") (pin "3") (pinfunction "VSS_3") (pintype "power_in"))
      (node (ref "U9") (pin "11") (pinfunction "V-_11") (pintype "power_in"))
      (node (ref "X1") (pin "3") (pinfunction "3_3") (pintype "passive"))
      (node (ref "X1") (pin "6") (pinfunction "6_6") (pintype "passive"))
      (node (ref "X1") (pin "7") (pinfunction "7_7") (pintype "passive"))
      (node (ref "X2") (pin "3") (pinfunction "3_3") (pintype "passive"))
      (node (ref "X2") (pin "6") (pinfunction "6_6") (pintype "passive"))
      (node (ref "X2") (pin "7") (pinfunction "7_7") (pintype "passive"))
      (node (ref "X5") (pin "2") (pinfunction "2_2") (pintype "passive"))
    )
    (net (code "18") (name "I2CSCL") (class "Default")
      (node (ref "G1") (pin "PB6") (pinfunction "PB6_PB6") (pintype "bidirectional"))
      (node (ref "JP6") (pin "1") (pinfunction "1_1") (pintype "passive"))
      (node (ref "R15") (pin "2") (pinfunction "2_2") (pintype "passive"))
    )
    (net (code "19") (name "I2CSDA") (class "Default")
      (node (ref "G1") (pin "PB7") (pinfunction "PB7_PB7") (pintype "bidirectional"))
      (node (ref "JP6") (pin "2") (pinfunction "2_2") (pintype "passive"))
      (node (ref "R14") (pin "2") (pinfunction "2_2") (pintype "passive"))
    )
    (net (code "20") (name "ILAT") (class "Default")
      (node (ref "G1") (pin "PA6") (pinfunction "PA6_PA6") (pintype "bidirectional"))
      (node (ref "U3") (pin "15") (pinfunction "SH/~{LD}_15") (pintype "input"))
      (node (ref "U4") (pin "15") (pinfunction "SH/~{LD}_15") (pintype "input"))
    )
    (net (code "21") (name "MISO") (class "Default")
      (node (ref "G1") (pin "PB4") (pinfunction "PB4_PB4") (pintype "bidirectional"))
      (node (ref "JP5") (pin "1") (pinfunction "1_1") (pintype "passive"))
    )
    (net (code "22") (name "MISO2") (class "Default")
      (node (ref "G1") (pin "PC2") (pinfunction "PC2_PC2") (pintype "bidirectional"))
      (node (ref "SJ1") (pin "P$2") (pinfunction "2_P$2") (pintype "passive"))
      (node (ref "SJ6") (pin "P$2") (pinfunction "2_P$2") (pintype "passive"))
      (node (ref "U3") (pin "13") (pinfunction "QH_13") (pintype "output"))
    )
    (net (code "23") (name "MOSI") (class "Default")
      (node (ref "G1") (pin "PB5") (pinfunction "PB5_PB5") (pintype "bidirectional"))
      (node (ref "R4") (pin "1") (pinfunction "1_1") (pintype "passive"))
      (node (ref "SJ13") (pin "P$2") (pinfunction "2_P$2") (pintype "passive"))
      (node (ref "SJ3") (pin "1") (pinfunction "1_1") (pintype "passive"))
      (node (ref "U13") (pin "14") (pinfunction "SER_14") (pintype "input"))
    )
    (net (code "24") (name "Net-(D1-PadA)") (class "Default")
      (node (ref "D1") (pin "A") (pinfunction "A_A") (pintype "passive"))
      (node (ref "D2") (pin "A") (pinfunction "A_A") (pintype "passive"))
      (node (ref "JP7") (pin "4") (pinfunction "4_4") (pintype "passive"))
    )
    (net (code "25") (name "Net-(D1-PadC)") (class "Default")
      (node (ref "D1") (pin "C") (pinfunction "C_C") (pintype "passive"))
      (node (ref "D2") (pin "C") (pinfunction "C_C") (pintype "passive"))
      (node (ref "JP7") (pin "1") (pinfunction "1_1") (pintype "passive"))
    )
    (net (code "26") (name "Net-(IC1-OUT)") (class "Default")
      (node (ref "D3") (pin "C") (pinfunction "C_C") (pintype "passive"))
      (node (ref "D4") (pin "C") (pinfunction "C_C") (pintype "passive"))
      (node (ref "IC1") (pin "7") (pinfunction "OUT_7") (pintype "passive"))
      (node (ref "L1") (pin "2") (pinfunction "2_2") (pintype "passive"))
      (node (ref "U2") (pin "2") (pinfunction "VOUT_2") (pintype "bidirectional"))
    )
    (net (code "27") (name "Net-(IC2-RS)") (class "Default")
      (node (ref "IC2") (pin "8") (pinfunction "RS_8") (pintype "bidirectional"))
      (node (ref "R16") (pin "1") (pinfunction "1_1") (pintype "passive"))
      (node (ref "U1") (pin "8") (pinfunction "RS_8") (pintype "input"))
    )
    (net (code "28") (name "Net-(IC2-VREF)") (class "Default")
      (node (ref "IC2") (pin "5") (pinfunction "VREF_5") (pintype "bidirectional"))
      (node (ref "SJ5") (pin "P$2") (pinfunction "2_P$2") (pintype "passive"))
      (node (ref "U1") (pin "5") (pinfunction "VREF_5") (pintype "output"))
    )
    (net (code "29") (name "Net-(JP7-Pad3)") (class "Default")
      (node (ref "JP7") (pin "3") (pinfunction "3_3") (pintype "passive"))
      (node (ref "R17") (pin "1") (pinfunction "1_1") (pintype "passive"))
    )
    (net (code "30") (name "Net-(JP8-Pad1)") (class "Default")
      (node (ref "JP8") (pin "1") (pinfunction "1_1") (pintype "passive"))
      (node (ref "R25") (pin "2") (pinfunction "2_2") (pintype "passive"))
      (node (ref "R26") (pin "2") (pinfunction "2_2") (pintype "passive"))
      (node (ref "RN1") (pin "9") (pinfunction "9_9") (pintype "passive"))
      (node (ref "RN2") (pin "1") (pinfunction "1_1") (pintype "passive"))
      (node (ref "X3") (pin "1") (pinfunction "1_1") (pintype "passive"))
    )
    (net (code "31") (name "Net-(JP9-Pad1)") (class "Default")
      (node (ref "JP9") (pin "1") (pinfunction "1_1") (pintype "passive"))
      (node (ref "R41") (pin "2") (pinfunction "2_2") (pintype "passive"))
      (node (ref "R42") (pin "2") (pinfunction "2_2") (pintype "passive"))
      (node (ref "RN3") (pin "9") (pinfunction "9_9") (pintype "passive"))
      (node (ref "RN4") (pin "1") (pinfunction "1_1") (pintype "passive"))
      (node (ref "X4") (pin "1") (pinfunction "1_1") (pintype "passive"))
    )
    (net (code "32") (name "Net-(Q1-D)") (class "Default")
      (node (ref "Q1") (pin "3") (pinfunction "D_3") (pintype "passive"))
      (node (ref "U12") (pin "11") (pinfunction "O8_11") (pintype "open_collector"))
      (node (ref "X7") (pin "8") (pinfunction "8_8") (pintype "passive"))
    )
    (net (code "33") (name "Net-(Q1-G)") (class "Default")
      (node (ref "Q1") (pin "1") (pinfunction "G_1") (pintype "passive"))
      (node (ref "R52") (pin "2") (pinfunction "2_2") (pintype "passive"))
    )
    (net (code "34") (name "Net-(Q2-D)") (class "Default")
      (node (ref "Q2") (pin "3") (pinfunction "D_3") (pintype "passive"))
      (node (ref "U12") (pin "12") (pinfunction "O7_12") (pintype "open_collector"))
      (node (ref "X7") (pin "7") (pinfunction "7_7") (pintype "passive"))
    )
    (net (code "35") (name "Net-(Q2-G)") (class "Default")
      (node (ref "Q2") (pin "1") (pinfunction "G_1") (pintype "passive"))
      (node (ref "R53") (pin "2") (pinfunction "2_2") (pintype "passive"))
    )
    (net (code "36") (name "Net-(Q3-D)") (class "Default")
      (node (ref "Q3") (pin "3") (pinfunction "D_3") (pintype "passive"))
      (node (ref "U12") (pin "13") (pinfunction "O6_13") (pintype "open_collector"))
      (node (ref "X7") (pin "6") (pinfunction "6_6") (pintype "passive"))
    )
    (net (code "37") (name "Net-(Q3-G)") (class "Default")
      (node (ref "Q3") (pin "1") (pinfunction "G_1") (pintype "passive"))
      (node (ref "R54") (pin "2") (pinfunction "2_2") (pintype "passive"))
    )
    (net (code "38") (name "Net-(Q4-D)") (class "Default")
      (node (ref "Q4") (pin "3") (pinfunction "D_3") (pintype "passive"))
      (node (ref "U12") (pin "14") (pinfunction "O5_14") (pintype "open_collector"))
      (node (ref "X7") (pin "5") (pinfunction "5_5") (pintype "passive"))
    )
    (net (code "39") (name "Net-(Q4-G)") (class "Default")
      (node (ref "Q4") (pin "1") (pinfunction "G_1") (pintype "passive"))
      (node (ref "R55") (pin "2") (pinfunction "2_2") (pintype "passive"))
    )
    (net (code "40") (name "Net-(Q5-D)") (class "Default")
      (node (ref "Q5") (pin "3") (pinfunction "D_3") (pintype "passive"))
      (node (ref "U12") (pin "15") (pinfunction "O4_15") (pintype "open_collector"))
      (node (ref "X7") (pin "4") (pinfunction "4_4") (pintype "passive"))
    )
    (net (code "41") (name "Net-(Q5-G)") (class "Default")
      (node (ref "Q5") (pin "1") (pinfunction "G_1") (pintype "passive"))
      (node (ref "R56") (pin "2") (pinfunction "2_2") (pintype "passive"))
    )
    (net (code "42") (name "Net-(Q6-D)") (class "Default")
      (node (ref "Q6") (pin "3") (pinfunction "D_3") (pintype "passive"))
      (node (ref "U12") (pin "16") (pinfunction "O3_16") (pintype "open_collector"))
      (node (ref "X7") (pin "3") (pinfunction "3_3") (pintype "passive"))
    )
    (net (code "43") (name "Net-(Q6-G)") (class "Default")
      (node (ref "Q6") (pin "1") (pinfunction "G_1") (pintype "passive"))
      (node (ref "R57") (pin "2") (pinfunction "2_2") (pintype "passive"))
    )
    (net (code "44") (name "Net-(Q7-D)") (class "Default")
      (node (ref "Q7") (pin "3") (pinfunction "D_3") (pintype "passive"))
      (node (ref "U12") (pin "17") (pinfunction "O2_17") (pintype "open_collector"))
      (node (ref "X7") (pin "2") (pinfunction "2_2") (pintype "passive"))
    )
    (net (code "45") (name "Net-(Q7-G)") (class "Default")
      (node (ref "Q7") (pin "1") (pinfunction "G_1") (pintype "passive"))
      (node (ref "R58") (pin "2") (pinfunction "2_2") (pintype "passive"))
    )
    (net (code "46") (name "Net-(Q8-D)") (class "Default")
      (node (ref "Q8") (pin "3") (pinfunction "D_3") (pintype "passive"))
      (node (ref "U12") (pin "18") (pinfunction "O1_18") (pintype "open_collector"))
      (node (ref "X7") (pin "1") (pinfunction "1_1") (pintype "passive"))
    )
    (net (code "47") (name "Net-(Q8-G)") (class "Default")
      (node (ref "Q8") (pin "1") (pinfunction "G_1") (pintype "passive"))
      (node (ref "R59") (pin "2") (pinfunction "2_2") (pintype "passive"))
    )
    (net (code "48") (name "Net-(Q9-D)") (class "Default")
      (node (ref "Q9") (pin "3") (pinfunction "D_3") (pintype "passive"))
      (node (ref "U14") (pin "11") (pinfunction "O8_11") (pintype "open_collector"))
      (node (ref "X8") (pin "8") (pinfunction "8_8") (pintype "passive"))
    )
    (net (code "49") (name "Net-(Q9-G)") (class "Default")
      (node (ref "Q9") (pin "1") (pinfunction "G_1") (pintype "passive"))
      (node (ref "R60") (pin "2") (pinfunction "2_2") (pintype "passive"))
    )
    (net (code "50") (name "Net-(Q10-D)") (class "Default")
      (node (ref "Q10") (pin "3") (pinfunction "D_3") (pintype "passive"))
      (node (ref "U14") (pin "12") (pinfunction "O7_12") (pintype "open_collector"))
      (node (ref "X8") (pin "7") (pinfunction "7_7") (pintype "passive"))
    )
    (net (code "51") (name "Net-(Q10-G)") (class "Default")
      (node (ref "Q10") (pin "1") (pinfunction "G_1") (pintype "passive"))
      (node (ref "R61") (pin "2") (pinfunction "2_2") (pintype "passive"))
    )
    (net (code "52") (name "Net-(Q11-D)") (class "Default")
      (node (ref "Q11") (pin "3") (pinfunction "D_3") (pintype "passive"))
      (node (ref "U14") (pin "13") (pinfunction "O6_13") (pintype "open_collector"))
      (node (ref "X8") (pin "6") (pinfunction "6_6") (pintype "passive"))
    )
    (net (code "53") (name "Net-(Q11-G)") (class "Default")
      (node (ref "Q11") (pin "1") (pinfunction "G_1") (pintype "passive"))
      (node (ref "R62") (pin "2") (pinfunction "2_2") (pintype "passive"))
    )
    (net (code "54") (name "Net-(Q12-D)") (class "Default")
      (node (ref "Q12") (pin "3") (pinfunction "D_3") (pintype "passive"))
      (node (ref "U14") (pin "14") (pinfunction "O5_14") (pintype "open_collector"))
      (node (ref "X8") (pin "5") (pinfunction "5_5") (pintype "passive"))
    )
    (net (code "55") (name "Net-(Q12-G)") (class "Default")
      (node (ref "Q12") (pin "1") (pinfunction "G_1") (pintype "passive"))
      (node (ref "R63") (pin "2") (pinfunction "2_2") (pintype "passive"))
    )
    (net (code "56") (name "Net-(Q13-D)") (class "Default")
      (node (ref "Q13") (pin "3") (pinfunction "D_3") (pintype "passive"))
      (node (ref "U14") (pin "15") (pinfunction "O4_15") (pintype "open_collector"))
      (node (ref "X8") (pin "4") (pinfunction "4_4") (pintype "passive"))
    )
    (net (code "57") (name "Net-(Q13-G)") (class "Default")
      (node (ref "Q13") (pin "1") (pinfunction "G_1") (pintype "passive"))
      (node (ref "R64") (pin "2") (pinfunction "2_2") (pintype "passive"))
    )
    (net (code "58") (name "Net-(Q14-D)") (class "Default")
      (node (ref "Q14") (pin "3") (pinfunction "D_3") (pintype "passive"))
      (node (ref "U14") (pin "16") (pinfunction "O3_16") (pintype "open_collector"))
      (node (ref "X8") (pin "3") (pinfunction "3_3") (pintype "passive"))
    )
    (net (code "59") (name "Net-(Q14-G)") (class "Default")
      (node (ref "Q14") (pin "1") (pinfunction "G_1") (pintype "passive"))
      (node (ref "R65") (pin "2") (pinfunction "2_2") (pintype "passive"))
    )
    (net (code "60") (name "Net-(Q15-D)") (class "Default")
      (node (ref "Q15") (pin "3") (pinfunction "D_3") (pintype "passive"))
      (node (ref "U14") (pin "17") (pinfunction "O2_17") (pintype "open_collector"))
      (node (ref "X8") (pin "2") (pinfunction "2_2") (pintype "passive"))
    )
    (net (code "61") (name "Net-(Q15-G)") (class "Default")
      (node (ref "Q15") (pin "1") (pinfunction "G_1") (pintype "passive"))
      (node (ref "R66") (pin "2") (pinfunction "2_2") (pintype "passive"))
    )
    (net (code "62") (name "Net-(Q16-D)") (class "Default")
      (node (ref "Q16") (pin "3") (pinfunction "D_3") (pintype "passive"))
      (node (ref "U14") (pin "18") (pinfunction "O1_18") (pintype "open_collector"))
      (node (ref "X8") (pin "1") (pinfunction "1_1") (pintype "passive"))
    )
    (net (code "63") (name "Net-(Q16-G)") (class "Default")
      (node (ref "Q16") (pin "1") (pinfunction "G_1") (pintype "passive"))
      (node (ref "R67") (pin "2") (pinfunction "2_2") (pintype "passive"))
    )
    (net (code "64") (name "Net-(RN2A-2)") (class "Default")
      (node (ref "R25") (pin "1") (pinfunction "1_1") (pintype "passive"))
      (node (ref "RN2") (pin "16") (pinfunction "2_16") (pintype "passive"))
      (node (ref "U3") (pin "14") (pinfunction "H_14") (pintype "input"))
    )
    (net (code "65") (name "Net-(RN2B-1)") (class "Default")
      (node (ref "JP8") (pin "2") (pinfunction "2_2") (pintype "passive"))
      (node (ref "R24") (pin "2") (pinfunction "2_2") (pintype "passive"))
      (node (ref "R27") (pin "2") (pinfunction "2_2") (pintype "passive"))
      (node (ref "RN1") (pin "8") (pinfunction "8_8") (pintype "passive"))
      (node (ref "RN2") (pin "2") (pinfunction "1_2") (pintype "passive"))
      (node (ref "X3") (pin "2") (pinfunction "2_2") (pintype "passive"))
    )
    (net (code "66") (name "Net-(RN2B-2)") (class "Default")
      (node (ref "R24") (pin "1") (pinfunction "1_1") (pintype "passive"))
      (node (ref "RN2") (pin "15") (pinfunction "2_15") (pintype "passive"))
      (node (ref "U3") (pin "12") (pinfunction "G_12") (pintype "input"))
    )
    (net (code "67") (name "Net-(RN2C-1)") (class "Default")
      (node (ref "JP8") (pin "3") (pinfunction "3_3") (pintype "passive"))
      (node (ref "R23") (pin "2") (pinfunction "2_2") (pintype "passive"))
      (node (ref "R28") (pin "2") (pinfunction "2_2") (pintype "passive"))
      (node (ref "RN1") (pin "7") (pinfunction "7_7") (pintype "passive"))
      (node (ref "RN2") (pin "3") (pinfunction "1_3") (pintype "passive"))
      (node (ref "X3") (pin "3") (pinfunction "3_3") (pintype "passive"))
    )
    (net (code "68") (name "Net-(RN2C-2)") (class "Default")
      (node (ref "R23") (pin "1") (pinfunction "1_1") (pintype "passive"))
      (node (ref "RN2") (pin "14") (pinfunction "2_14") (pintype "passive"))
      (node (ref "U3") (pin "11") (pinfunction "F_11") (pintype "input"))
    )
    (net (code "69") (name "Net-(RN2D-1)") (class "Default")
      (node (ref "JP8") (pin "4") (pinfunction "4_4") (pintype "passive"))
      (node (ref "R22") (pin "2") (pinfunction "2_2") (pintype "passive"))
      (node (ref "R29") (pin "2") (pinfunction "2_2") (pintype "passive"))
      (node (ref "RN1") (pin "6") (pinfunction "6_6") (pintype "passive"))
      (node (ref "RN2") (pin "4") (pinfunction "1_4") (pintype "passive"))
      (node (ref "X3") (pin "4") (pinfunction "4_4") (pintype "passive"))
    )
    (net (code "70") (name "Net-(RN2D-2)") (class "Default")
      (node (ref "R22") (pin "1") (pinfunction "1_1") (pintype "passive"))
      (node (ref "RN2") (pin "13") (pinfunction "2_13") (pintype "passive"))
      (node (ref "U3") (pin "10") (pinfunction "E_10") (pintype "input"))
    )
    (net (code "71") (name "Net-(RN2E-1)") (class "Default")
      (node (ref "JP8") (pin "7") (pinfunction "7_7") (pintype "passive"))
      (node (ref "R21") (pin "2") (pinfunction "2_2") (pintype "passive"))
      (node (ref "R30") (pin "2") (pinfunction "2_2") (pintype "passive"))
      (node (ref "RN1") (pin "5") (pinfunction "5_5") (pintype "passive"))
      (node (ref "RN2") (pin "5") (pinfunction "1_5") (pintype "passive"))
      (node (ref "X3") (pin "5") (pinfunction "5_5") (pintype "passive"))
    )
    (net (code "72") (name "Net-(RN2E-2)") (class "Default")
      (node (ref "R21") (pin "1") (pinfunction "1_1") (pintype "passive"))
      (node (ref "RN2") (pin "12") (pinfunction "2_12") (pintype "passive"))
      (node (ref "U3") (pin "5") (pinfunction "D_5") (pintype "input"))
    )
    (net (code "73") (name "Net-(RN2F-1)") (class "Default")
      (node (ref "JP8") (pin "8") (pinfunction "8_8") (pintype "passive"))
      (node (ref "R20") (pin "2") (pinfunction "2_2") (pintype "passive"))
      (node (ref "R31") (pin "2") (pinfunction "2_2") (pintype "passive"))
      (node (ref "RN1") (pin "4") (pinfunction "4_4") (pintype "passive"))
      (node (ref "RN2") (pin "6") (pinfunction "1_6") (pintype "passive"))
      (node (ref "X3") (pin "6") (pinfunction "6_6") (pintype "passive"))
    )
    (net (code "74") (name "Net-(RN2F-2)") (class "Default")
      (node (ref "R20") (pin "1") (pinfunction "1_1") (pintype "passive"))
      (node (ref "RN2") (pin "11") (pinfunction "2_11") (pintype "passive"))
      (node (ref "U3") (pin "4") (pinfunction "C_4") (pintype "input"))
    )
    (net (code "75") (name "Net-(RN2G-1)") (class "Default")
      (node (ref "JP8") (pin "9") (pinfunction "9_9") (pintype "passive"))
      (node (ref "R19") (pin "2") (pinfunction "2_2") (pintype "passive"))
      (node (ref "R32") (pin "2") (pinfunction "2_2") (pintype "passive"))
      (node (ref "RN1") (pin "3") (pinfunction "3_3") (pintype "passive"))
      (node (ref "RN2") (pin "7") (pinfunction "1_7") (pintype "passive"))
      (node (ref "X3") (pin "7") (pinfunction "7_7") (pintype "passive"))
    )
    (net (code "76") (name "Net-(RN2G-2)") (class "Default")
      (node (ref "R19") (pin "1") (pinfunction "1_1") (pintype "passive"))
      (node (ref "RN2") (pin "10") (pinfunction "2_10") (pintype "passive"))
      (node (ref "U3") (pin "3") (pinfunction "B_3") (pintype "input"))
    )
    (net (code "77") (name "Net-(RN2H-1)") (class "Default")
      (node (ref "JP8") (pin "10") (pinfunction "10_10") (pintype "passive"))
      (node (ref "R18") (pin "2") (pinfunction "2_2") (pintype "passive"))
      (node (ref "R33") (pin "2") (pinfunction "2_2") (pintype "passive"))
      (node (ref "RN1") (pin "2") (pinfunction "2_2") (pintype "passive"))
      (node (ref "RN2") (pin "8") (pinfunction "1_8") (pintype "passive"))
      (node (ref "X3") (pin "8") (pinfunction "8_8") (pintype "passive"))
    )
    (net (code "78") (name "Net-(RN2H-2)") (class "Default")
      (node (ref "R18") (pin "1") (pinfunction "1_1") (pintype "passive"))
      (node (ref "RN2") (pin "9") (pinfunction "2_9") (pintype "passive"))
      (node (ref "U3") (pin "2") (pinfunction "A_2") (pintype "input"))
    )
    (net (code "79") (name "Net-(RN4A-2)") (class "Default")
      (node (ref "R41") (pin "1") (pinfunction "1_1") (pintype "passive"))
      (node (ref "RN4") (pin "16") (pinfunction "2_16") (pintype "passive"))
      (node (ref "U4") (pin "14") (pinfunction "H_14") (pintype "input"))
    )
    (net (code "80") (name "Net-(RN4B-1)") (class "Default")
      (node (ref "JP9") (pin "2") (pinfunction "2_2") (pintype "passive"))
      (node (ref "R40") (pin "2") (pinfunction "2_2") (pintype "passive"))
      (node (ref "R43") (pin "2") (pinfunction "2_2") (pintype "passive"))
      (node (ref "RN3") (pin "8") (pinfunction "8_8") (pintype "passive"))
      (node (ref "RN4") (pin "2") (pinfunction "1_2") (pintype "passive"))
      (node (ref "X4") (pin "2") (pinfunction "2_2") (pintype "passive"))
    )
    (net (code "81") (name "Net-(RN4B-2)") (class "Default")
      (node (ref "R40") (pin "1") (pinfunction "1_1") (pintype "passive"))
      (node (ref "RN4") (pin "15") (pinfunction "2_15") (pintype "passive"))
      (node (ref "U4") (pin "12") (pinfunction "G_12") (pintype "input"))
    )
    (net (code "82") (name "Net-(RN4C-1)") (class "Default")
      (node (ref "JP9") (pin "3") (pinfunction "3_3") (pintype "passive"))
      (node (ref "R39") (pin "2") (pinfunction "2_2") (pintype "passive"))
      (node (ref "R44") (pin "2") (pinfunction "2_2") (pintype "passive"))
      (node (ref "RN3") (pin "7") (pinfunction "7_7") (pintype "passive"))
      (node (ref "RN4") (pin "3") (pinfunction "1_3") (pintype "passive"))
      (node (ref "X4") (pin "3") (pinfunction "3_3") (pintype "passive"))
    )
    (net (code "83") (name "Net-(RN4C-2)") (class "Default")
      (node (ref "R39") (pin "1") (pinfunction "1_1") (pintype "passive"))
      (node (ref "RN4") (pin "14") (pinfunction "2_14") (pintype "passive"))
      (node (ref "U4") (pin "11") (pinfunction "F_11") (pintype "input"))
    )
    (net (code "84") (name "Net-(RN4D-1)") (class "Default")
      (node (ref "JP9") (pin "4") (pinfunction "4_4") (pintype "passive"))
      (node (ref "R38") (pin "2") (pinfunction "2_2") (pintype "passive"))
      (node (ref "R45") (pin "2") (pinfunction "2_2") (pintype "passive"))
      (node (ref "RN3") (pin "6") (pinfunction "6_6") (pintype "passive"))
      (node (ref "RN4") (pin "4") (pinfunction "1_4") (pintype "passive"))
      (node (ref "X4") (pin "4") (pinfunction "4_4") (pintype "passive"))
    )
    (net (code "85") (name "Net-(RN4D-2)") (class "Default")
      (node (ref "R38") (pin "1") (pinfunction "1_1") (pintype "passive"))
      (node (ref "RN4") (pin "13") (pinfunction "2_13") (pintype "passive"))
      (node (ref "U4") (pin "10") (pinfunction "E_10") (pintype "input"))
    )
    (net (code "86") (name "Net-(RN4E-1)") (class "Default")
      (node (ref "JP9") (pin "7") (pinfunction "7_7") (pintype "passive"))
      (node (ref "R37") (pin "2") (pinfunction "2_2") (pintype "passive"))
      (node (ref "R46") (pin "2") (pinfunction "2_2") (pintype "passive"))
      (node (ref "RN3") (pin "5") (pinfunction "5_5") (pintype "passive"))
      (node (ref "RN4") (pin "5") (pinfunction "1_5") (pintype "passive"))
      (node (ref "X4") (pin "5") (pinfunction "5_5") (pintype "passive"))
    )
    (net (code "87") (name "Net-(RN4E-2)") (class "Default")
      (node (ref "R37") (pin "1") (pinfunction "1_1") (pintype "passive"))
      (node (ref "RN4") (pin "12") (pinfunction "2_12") (pintype "passive"))
      (node (ref "U4") (pin "5") (pinfunction "D_5") (pintype "input"))
    )
    (net (code "88") (name "Net-(RN4F-1)") (class "Default")
      (node (ref "JP9") (pin "8") (pinfunction "8_8") (pintype "passive"))
      (node (ref "R36") (pin "2") (pinfunction "2_2") (pintype "passive"))
      (node (ref "R47") (pin "2") (pinfunction "2_2") (pintype "passive"))
      (node (ref "RN3") (pin "4") (pinfunction "4_4") (pintype "passive"))
      (node (ref "RN4") (pin "6") (pinfunction "1_6") (pintype "passive"))
      (node (ref "X4") (pin "6") (pinfunction "6_6") (pintype "passive"))
    )
    (net (code "89") (name "Net-(RN4F-2)") (class "Default")
      (node (ref "R36") (pin "1") (pinfunction "1_1") (pintype "passive"))
      (node (ref "RN4") (pin "11") (pinfunction "2_11") (pintype "passive"))
      (node (ref "U4") (pin "4") (pinfunction "C_4") (pintype "input"))
    )
    (net (code "90") (name "Net-(RN4G-1)") (class "Default")
      (node (ref "JP9") (pin "9") (pinfunction "9_9") (pintype "passive"))
      (node (ref "R35") (pin "2") (pinfunction "2_2") (pintype "passive"))
      (node (ref "R48") (pin "2") (pinfunction "2_2") (pintype "passive"))
      (node (ref "RN3") (pin "3") (pinfunction "3_3") (pintype "passive"))
      (node (ref "RN4") (pin "7") (pinfunction "1_7") (pintype "passive"))
      (node (ref "X4") (pin "7") (pinfunction "7_7") (pintype "passive"))
    )
    (net (code "91") (name "Net-(RN4G-2)") (class "Default")
      (node (ref "R35") (pin "1") (pinfunction "1_1") (pintype "passive"))
      (node (ref "RN4") (pin "10") (pinfunction "2_10") (pintype "passive"))
      (node (ref "U4") (pin "3") (pinfunction "B_3") (pintype "input"))
    )
    (net (code "92") (name "Net-(RN4H-1)") (class "Default")
      (node (ref "JP9") (pin "10") (pinfunction "10_10") (pintype "passive"))
      (node (ref "R34") (pin "2") (pinfunction "2_2") (pintype "passive"))
      (node (ref "R49") (pin "2") (pinfunction "2_2") (pintype "passive"))
      (node (ref "RN3") (pin "2") (pinfunction "2_2") (pintype "passive"))
      (node (ref "RN4") (pin "8") (pinfunction "1_8") (pintype "passive"))
      (node (ref "X4") (pin "8") (pinfunction "8_8") (pintype "passive"))
    )
    (net (code "93") (name "Net-(RN4H-2)") (class "Default")
      (node (ref "R34") (pin "1") (pinfunction "1_1") (pintype "passive"))
      (node (ref "RN4") (pin "9") (pinfunction "2_9") (pintype "passive"))
      (node (ref "U4") (pin "2") (pinfunction "A_2") (pintype "input"))
    )
    (net (code "94") (name "Net-(SJ1-1)") (class "Default")
      (node (ref "G1") (pin "PB14") (pinfunction "PB14_PB14") (pintype "bidirectional"))
      (node (ref "SJ1") (pin "P$1") (pinfunction "1_P$1") (pintype "passive"))
    )
    (net (code "95") (name "Net-(SJ2-1)") (class "Default")
      (node (ref "G1") (pin "VIN2") (pinfunction "VIN2_VIN2") (pintype "power_in"))
      (node (ref "SJ2") (pin "P$1") (pinfunction "1_P$1") (pintype "passive"))
    )
    (net (code "96") (name "Net-(SJ4-2)") (class "Default")
      (node (ref "JP5") (pin "2") (pinfunction "2_2") (pintype "passive"))
      (node (ref "SJ3") (pin "2") (pinfunction "2_2") (pintype "passive"))
      (node (ref "SJ4") (pin "P$2") (pinfunction "2_P$2") (pintype "passive"))
    )
    (net (code "97") (name "Net-(SJ7-1)") (class "Default")
      (node (ref "SJ11") (pin "1") (pinfunction "1_1") (pintype "passive"))
      (node (ref "SJ7") (pin "P$1") (pinfunction "1_P$1") (pintype "passive"))
      (node (ref "SJ9") (pin "P$1") (pinfunction "1_P$1") (pintype "passive"))
      (node (ref "U12") (pin "9") (pinfunction "GND_9") (pintype "power_in"))
    )
    (net (code "98") (name "Net-(SJ10-1)") (class "Default")
      (node (ref "SJ10") (pin "P$1") (pinfunction "1_P$1") (pintype "passive"))
      (node (ref "SJ12") (pin "P$1") (pinfunction "1_P$1") (pintype "passive"))
      (node (ref "SJ8") (pin "P$1") (pinfunction "1_P$1") (pintype "passive"))
      (node (ref "U12") (pin "10") (pinfunction "CD+_10") (pintype "passive"))
      (node (ref "X7") (pin "9") (pinfunction "9_9") (pintype "passive"))
    )
    (net (code "99") (name "Net-(SJ14-1)") (class "Default")
      (node (ref "SJ14") (pin "P$1") (pinfunction "1_P$1") (pintype "passive"))
      (node (ref "SJ16") (pin "P$1") (pinfunction "1_P$1") (pintype "passive"))
      (node (ref "SJ18") (pin "1") (pinfunction "1_1") (pintype "passive"))
      (node (ref "U14") (pin "9") (pinfunction "GND_9") (pintype "power_in"))
    )
    (net (code "100") (name "Net-(SJ15-1)") (class "Default")
      (node (ref "SJ15") (pin "P$1") (pinfunction "1_P$1") (pintype "passive"))
      (node (ref "SJ17") (pin "P$1") (pinfunction "1_P$1") (pintype "passive"))
      (node (ref "SJ19") (pin "P$1") (pinfunction "1_P$1") (pintype "passive"))
      (node (ref "U14") (pin "10") (pinfunction "CD+_10") (pintype "passive"))
      (node (ref "X8") (pin "9") (pinfunction "9_9") (pintype "passive"))
    )
    (net (code "101") (name "Net-(SJ20-2)") (class "Default")
      (node (ref "G1") (pin "PB13") (pinfunction "PB13_PB13") (pintype "bidirectional"))
      (node (ref "SJ20") (pin "P$2") (pinfunction "2_P$2") (pintype "passive"))
    )
    (net (code "102") (name "Net-(U5A-O)") (class "Default")
      (node (ref "JP10") (pin "1") (pinfunction "1_1") (pintype "passive"))
      (node (ref "U5") (pin "7") (pinfunction "O_7") (pintype "output"))
      (node (ref "U6") (pin "7") (pinfunction "OUT_7") (pintype "output"))
      (node (ref "X6") (pin "1") (pinfunction "1_1") (pintype "passive"))
    )
    (net (code "103") (name "Net-(U5B-O)") (class "Default")
      (node (ref "JP10") (pin "2") (pinfunction "2_2") (pintype "passive"))
      (node (ref "U5") (pin "5") (pinfunction "O_5") (pintype "output"))
      (node (ref "U6") (pin "8") (pinfunction "OUT_8") (pintype "output"))
      (node (ref "X6") (pin "2") (pinfunction "2_2") (pintype "passive"))
    )
    (net (code "104") (name "Net-(U6A--IN)") (class "Default")
      (node (ref "R50") (pin "1") (pinfunction "1_1") (pintype "passive"))
      (node (ref "R51") (pin "2") (pinfunction "2_2") (pintype "passive"))
      (node (ref "U6") (pin "13") (pinfunction "-IN_13") (pintype "input"))
      (node (ref "U6") (pin "2") (pinfunction "-IN_2") (pintype "input"))
      (node (ref "U6") (pin "6") (pinfunction "-IN_6") (pintype "input"))
      (node (ref "U6") (pin "9") (pinfunction "-IN_9") (pintype "input"))
      (node (ref "U9") (pin "13") (pinfunction "-IN_13") (pintype "input"))
      (node (ref "U9") (pin "2") (pinfunction "-IN_2") (pintype "input"))
      (node (ref "U9") (pin "6") (pinfunction "-IN_6") (pintype "input"))
      (node (ref "U9") (pin "9") (pinfunction "-IN_9") (pintype "input"))
    )
    (net (code "105") (name "Net-(U6A-OUT)") (class "Default")
      (node (ref "JP10") (pin "3") (pinfunction "3_3") (pintype "passive"))
      (node (ref "U6") (pin "1") (pinfunction "OUT_1") (pintype "output"))
      (node (ref "U7") (pin "5") (pinfunction "O_5") (pintype "output"))
      (node (ref "X6") (pin "3") (pinfunction "3_3") (pintype "passive"))
    )
    (net (code "106") (name "Net-(U6D-OUT)") (class "Default")
      (node (ref "JP10") (pin "4") (pinfunction "4_4") (pintype "passive"))
      (node (ref "U6") (pin "14") (pinfunction "OUT_14") (pintype "output"))
      (node (ref "U7") (pin "7") (pinfunction "O_7") (pintype "output"))
      (node (ref "X6") (pin "4") (pinfunction "4_4") (pintype "passive"))
    )
    (net (code "107") (name "Net-(U8A-O)") (class "Default")
      (node (ref "JP10") (pin "7") (pinfunction "7_7") (pintype "passive"))
      (node (ref "U8") (pin "7") (pinfunction "O_7") (pintype "output"))
      (node (ref "U9") (pin "7") (pinfunction "OUT_7") (pintype "output"))
      (node (ref "X6") (pin "5") (pinfunction "5_5") (pintype "passive"))
    )
    (net (code "108") (name "Net-(U8B-O)") (class "Default")
      (node (ref "JP10") (pin "8") (pinfunction "8_8") (pintype "passive"))
      (node (ref "U8") (pin "5") (pinfunction "O_5") (pintype "output"))
      (node (ref "U9") (pin "8") (pinfunction "OUT_8") (pintype "output"))
      (node (ref "X6") (pin "6") (pinfunction "6_6") (pintype "passive"))
    )
    (net (code "109") (name "Net-(U10A-O)") (class "Default")
      (node (ref "JP10") (pin "10") (pinfunction "10_10") (pintype "passive"))
      (node (ref "U10") (pin "7") (pinfunction "O_7") (pintype "output"))
      (node (ref "U9") (pin "14") (pinfunction "OUT_14") (pintype "output"))
      (node (ref "X6") (pin "8") (pinfunction "8_8") (pintype "passive"))
    )
    (net (code "110") (name "Net-(U10B-O)") (class "Default")
      (node (ref "JP10") (pin "9") (pinfunction "9_9") (pintype "passive"))
      (node (ref "U10") (pin "5") (pinfunction "O_5") (pintype "output"))
      (node (ref "U9") (pin "1") (pinfunction "OUT_1") (pintype "output"))
      (node (ref "X6") (pin "7") (pinfunction "7_7") (pintype "passive"))
    )
    (net (code "111") (name "Net-(U11A-QA)") (class "Default")
      (node (ref "R59") (pin "1") (pinfunction "1_1") (pintype "passive"))
      (node (ref "U11") (pin "15") (pinfunction "QA_15") (pintype "tri_state"))
      (node (ref "U12") (pin "1") (pinfunction "I1_1") (pintype "input"))
    )
    (net (code "112") (name "Net-(U11A-QB)") (class "Default")
      (node (ref "R58") (pin "1") (pinfunction "1_1") (pintype "passive"))
      (node (ref "U11") (pin "1") (pinfunction "QB_1") (pintype "tri_state"))
      (node (ref "U12") (pin "2") (pinfunction "I2_2") (pintype "input"))
    )
    (net (code "113") (name "Net-(U11A-QC)") (class "Default")
      (node (ref "R57") (pin "1") (pinfunction "1_1") (pintype "passive"))
      (node (ref "U11") (pin "2") (pinfunction "QC_2") (pintype "tri_state"))
      (node (ref "U12") (pin "3") (pinfunction "I3_3") (pintype "input"))
    )
    (net (code "114") (name "Net-(U11A-QD)") (class "Default")
      (node (ref "R56") (pin "1") (pinfunction "1_1") (pintype "passive"))
      (node (ref "U11") (pin "3") (pinfunction "QD_3") (pintype "tri_state"))
      (node (ref "U12") (pin "4") (pinfunction "I4_4") (pintype "input"))
    )
    (net (code "115") (name "Net-(U11A-QE)") (class "Default")
      (node (ref "R55") (pin "1") (pinfunction "1_1") (pintype "passive"))
      (node (ref "U11") (pin "4") (pinfunction "QE_4") (pintype "tri_state"))
      (node (ref "U12") (pin "5") (pinfunction "I5_5") (pintype "input"))
    )
    (net (code "116") (name "Net-(U11A-QF)") (class "Default")
      (node (ref "R54") (pin "1") (pinfunction "1_1") (pintype "passive"))
      (node (ref "U11") (pin "5") (pinfunction "QF_5") (pintype "tri_state"))
      (node (ref "U12") (pin "6") (pinfunction "I6_6") (pintype "input"))
    )
    (net (code "117") (name "Net-(U11A-QG)") (class "Default")
      (node (ref "R53") (pin "1") (pinfunction "1_1") (pintype "passive"))
      (node (ref "U11") (pin "6") (pinfunction "QG_6") (pintype "tri_state"))
      (node (ref "U12") (pin "7") (pinfunction "I7_7") (pintype "input"))
    )
    (net (code "118") (name "Net-(U11A-QH)") (class "Default")
      (node (ref "R52") (pin "1") (pinfunction "1_1") (pintype "passive"))
      (node (ref "U11") (pin "7") (pinfunction "QH_7") (pintype "tri_state"))
      (node (ref "U12") (pin "8") (pinfunction "I8_8") (pintype "input"))
    )
    (net (code "119") (name "Net-(U13A-QA)") (class "Default")
      (node (ref "R67") (pin "1") (pinfunction "1_1") (pintype "passive"))
      (node (ref "U13") (pin "15") (pinfunction "QA_15") (pintype "tri_state"))
      (node (ref "U14") (pin "1") (pinfunction "I1_1") (pintype "input"))
    )
    (net (code "120") (name "Net-(U13A-QB)") (class "Default")
      (node (ref "R66") (pin "1") (pinfunction "1_1") (pintype "passive"))
      (node (ref "U13") (pin "1") (pinfunction "QB_1") (pintype "tri_state"))
      (node (ref "U14") (pin "2") (pinfunction "I2_2") (pintype "input"))
    )
    (net (code "121") (name "Net-(U13A-QC)") (class "Default")
      (node (ref "R65") (pin "1") (pinfunction "1_1") (pintype "passive"))
      (node (ref "U13") (pin "2") (pinfunction "QC_2") (pintype "tri_state"))
      (node (ref "U14") (pin "3") (pinfunction "I3_3") (pintype "input"))
    )
    (net (code "122") (name "Net-(U13A-QD)") (class "Default")
      (node (ref "R64") (pin "1") (pinfunction "1_1") (pintype "passive"))
      (node (ref "U13") (pin "3") (pinfunction "QD_3") (pintype "tri_state"))
      (node (ref "U14") (pin "4") (pinfunction "I4_4") (pintype "input"))
    )
    (net (code "123") (name "Net-(U13A-QE)") (class "Default")
      (node (ref "R63") (pin "1") (pinfunction "1_1") (pintype "passive"))
      (node (ref "U13") (pin "4") (pinfunction "QE_4") (pintype "tri_state"))
      (node (ref "U14") (pin "5") (pinfunction "I5_5") (pintype "input"))
    )
    (net (code "124") (name "Net-(U13A-QF)") (class "Default")
      (node (ref "R62") (pin "1") (pinfunction "1_1") (pintype "passive"))
      (node (ref "U13") (pin "5") (pinfunction "QF_5") (pintype "tri_state"))
      (node (ref "U14") (pin "6") (pinfunction "I6_6") (pintype "input"))
    )
    (net (code "125") (name "Net-(U13A-QG)") (class "Default")
      (node (ref "R61") (pin "1") (pinfunction "1_1") (pintype "passive"))
      (node (ref "U13") (pin "6") (pinfunction "QG_6") (pintype "tri_state"))
      (node (ref "U14") (pin "7") (pinfunction "I7_7") (pintype "input"))
    )
    (net (code "126") (name "Net-(U13A-QH)") (class "Default")
      (node (ref "R60") (pin "1") (pinfunction "1_1") (pintype "passive"))
      (node (ref "U13") (pin "7") (pinfunction "QH_7") (pintype "tri_state"))
      (node (ref "U14") (pin "8") (pinfunction "I8_8") (pintype "input"))
    )
    (net (code "127") (name "Net-(X1-Pad4)") (class "Default")
      (node (ref "X1") (pin "4") (pinfunction "4_4") (pintype "passive"))
      (node (ref "X2") (pin "4") (pinfunction "4_4") (pintype "passive"))
    )
    (net (code "128") (name "Net-(X1-Pad5)") (class "Default")
      (node (ref "X1") (pin "5") (pinfunction "5_5") (pintype "passive"))
      (node (ref "X2") (pin "5") (pinfunction "5_5") (pintype "passive"))
    )
    (net (code "129") (name "OLAT") (class "Default")
      (node (ref "G1") (pin "PA8") (pinfunction "PA8_PA8") (pintype "bidirectional"))
      (node (ref "R3") (pin "1") (pinfunction "1_1") (pintype "passive"))
      (node (ref "U11") (pin "12") (pinfunction "RCK_12") (pintype "input"))
      (node (ref "U13") (pin "12") (pinfunction "RCK_12") (pintype "input"))
    )
    (net (code "130") (name "SCK") (class "Default")
      (node (ref "G1") (pin "PB3") (pinfunction "PB3_PB3") (pintype "bidirectional"))
      (node (ref "JP5") (pin "3") (pinfunction "3_3") (pintype "passive"))
      (node (ref "R5") (pin "1") (pinfunction "1_1") (pintype "passive"))
      (node (ref "U11") (pin "11") (pinfunction "SCK_11") (pintype "input"))
      (node (ref "U13") (pin "11") (pinfunction "SCK_11") (pintype "input"))
    )
    (net (code "131") (name "SCK2") (class "Default")
      (node (ref "G1") (pin "PB10") (pinfunction "PB10_PB10") (pintype "bidirectional"))
      (node (ref "SJ20") (pin "P$1") (pinfunction "1_P$1") (pintype "passive"))
      (node (ref "U3") (pin "7") (pinfunction "CLK_7") (pintype "input"))
      (node (ref "U4") (pin "7") (pinfunction "CLK_7") (pintype "input"))
    )
    (net (code "132") (name "SLNK1") (class "Default")
      (node (ref "SJ13") (pin "P$1") (pinfunction "1_P$1") (pintype "passive"))
      (node (ref "U11") (pin "14") (pinfunction "SER_14") (pintype "input"))
      (node (ref "U13") (pin "9") (pinfunction "QH*_9") (pintype "tri_state"))
    )
    (net (code "133") (name "SLNK2") (class "Default")
      (node (ref "SJ4") (pin "P$1") (pinfunction "1_P$1") (pintype "passive"))
      (node (ref "U11") (pin "9") (pinfunction "QH*_9") (pintype "tri_state"))
    )
    (net (code "134") (name "SLNK3") (class "Default")
      (node (ref "SJ6") (pin "P$1") (pinfunction "1_P$1") (pintype "passive"))
      (node (ref "U3") (pin "1") (pinfunction "SER_1") (pintype "input"))
      (node (ref "U4") (pin "13") (pinfunction "QH_13") (pintype "output"))
    )
    (net (code "135") (name "SRV1") (class "Default")
      (node (ref "G1") (pin "PC9") (pinfunction "PC9_PC9") (pintype "bidirectional"))
      (node (ref "JP4") (pin "2") (pinfunction "2_2") (pintype "passive"))
      (node (ref "R13") (pin "2") (pinfunction "2_2") (pintype "passive"))
    )
    (net (code "136") (name "SRV2") (class "Default")
      (node (ref "G1") (pin "PC7") (pinfunction "PC7_PC7") (pintype "bidirectional"))
      (node (ref "JP4") (pin "1") (pinfunction "1_1") (pintype "passive"))
      (node (ref "R12") (pin "2") (pinfunction "2_2") (pintype "passive"))
    )
    (net (code "137") (name "SRV3") (class "Default")
      (node (ref "G1") (pin "PC8") (pinfunction "PC8_PC8") (pintype "bidirectional"))
      (node (ref "JP3") (pin "2") (pinfunction "2_2") (pintype "passive"))
      (node (ref "R11") (pin "2") (pinfunction "2_2") (pintype "passive"))
    )
    (net (code "138") (name "SRV4") (class "Default")
      (node (ref "G1") (pin "PC6") (pinfunction "PC6_PC6") (pintype "bidirectional"))
      (node (ref "JP3") (pin "1") (pinfunction "1_1") (pintype "passive"))
      (node (ref "R10") (pin "2") (pinfunction "2_2") (pintype "passive"))
    )
    (net (code "139") (name "SRV5") (class "Default")
      (node (ref "G1") (pin "PF1-PH1") (pinfunction "PF1-PH1_PF1-PH1") (pintype "bidirectional"))
      (node (ref "JP2") (pin "2") (pinfunction "2_2") (pintype "passive"))
      (node (ref "R9") (pin "2") (pinfunction "2_2") (pintype "passive"))
    )
    (net (code "140") (name "SRV6") (class "Default")
      (node (ref "G1") (pin "PA15") (pinfunction "PA15_PA15") (pintype "bidirectional"))
      (node (ref "JP2") (pin "1") (pinfunction "1_1") (pintype "passive"))
      (node (ref "R8") (pin "2") (pinfunction "2_2") (pintype "passive"))
    )
    (net (code "141") (name "SRV7") (class "Default")
      (node (ref "G1") (pin "PC12") (pinfunction "PC12_PC12") (pintype "bidirectional"))
      (node (ref "JP1") (pin "2") (pinfunction "2_2") (pintype "passive"))
      (node (ref "R7") (pin "2") (pinfunction "2_2") (pintype "passive"))
    )
    (net (code "142") (name "SRV8") (class "Default")
      (node (ref "G1") (pin "PD2") (pinfunction "PD2_PD2") (pintype "bidirectional"))
      (node (ref "JP1") (pin "1") (pinfunction "1_1") (pintype "passive"))
      (node (ref "R6") (pin "2") (pinfunction "2_2") (pintype "passive"))
    )
    (net (code "143") (name "TDRV1") (class "Default")
      (node (ref "G1") (pin "PB12") (pinfunction "PB12_PB12") (pintype "bidirectional"))
      (node (ref "U10") (pin "2") (pinfunction "I_2") (pintype "input"))
      (node (ref "U9") (pin "12") (pinfunction "+IN_12") (pintype "input"))
    )
    (net (code "144") (name "TDRV2") (class "Default")
      (node (ref "G1") (pin "PB2") (pinfunction "PB2_PB2") (pintype "bidirectional"))
      (node (ref "U10") (pin "4") (pinfunction "I_4") (pintype "input"))
      (node (ref "U9") (pin "3") (pinfunction "+IN_3") (pintype "input"))
    )
    (net (code "145") (name "TDRV3") (class "Default")
      (node (ref "G1") (pin "PB15") (pinfunction "PB15_PB15") (pintype "bidirectional"))
      (node (ref "U8") (pin "4") (pinfunction "I_4") (pintype "input"))
      (node (ref "U9") (pin "10") (pinfunction "+IN_10") (pintype "input"))
    )
    (net (code "146") (name "TDRV4") (class "Default")
      (node (ref "G1") (pin "PB1") (pinfunction "PB1_PB1") (pintype "bidirectional"))
      (node (ref "U8") (pin "2") (pinfunction "I_2") (pintype "input"))
      (node (ref "U9") (pin "5") (pinfunction "+IN_5") (pintype "input"))
    )
    (net (code "147") (name "TDRV5") (class "Default")
      (node (ref "G1") (pin "PA0") (pinfunction "PA0_PA0") (pintype "bidirectional"))
      (node (ref "U6") (pin "12") (pinfunction "+IN_12") (pintype "input"))
      (node (ref "U7") (pin "2") (pinfunction "I_2") (pintype "input"))
    )
    (net (code "148") (name "TDRV6") (class "Default")
      (node (ref "G1") (pin "PA4") (pinfunction "PA4_PA4") (pintype "bidirectional"))
      (node (ref "U6") (pin "3") (pinfunction "+IN_3") (pintype "input"))
      (node (ref "U7") (pin "4") (pinfunction "I_4") (pintype "input"))
    )
    (net (code "149") (name "TDRV7") (class "Default")
      (node (ref "G1") (pin "PC3") (pinfunction "PC3_PC3") (pintype "bidirectional"))
      (node (ref "U5") (pin "4") (pinfunction "I_4") (pintype "input"))
      (node (ref "U6") (pin "10") (pinfunction "+IN_10") (pintype "input"))
    )
    (net (code "150") (name "TDRV8") (class "Default")
      (node (ref "G1") (pin "PC0") (pinfunction "PC0_PC0") (pintype "bidirectional"))
      (node (ref "U5") (pin "2") (pinfunction "I_2") (pintype "input"))
      (node (ref "U6") (pin "5") (pinfunction "+IN_5") (pintype "input"))
    )
    (net (code "151") (name "V+") (class "Default")
      (node (ref "C6") (pin "+") (pinfunction "+_+") (pintype "passive"))
      (node (ref "C7") (pin "1") (pinfunction "1_1") (pintype "passive"))
      (node (ref "G1") (pin "E5V") (pinfunction "E5V_E5V") (pintype "power_in"))
      (node (ref "IC1") (pin "1") (pinfunction "FB_1") (pintype "input"))
      (node (ref "L1") (pin "1") (pinfunction "1_1") (pintype "passive"))
      (node (ref "U2") (pin "3") (pinfunction "FB_3") (pintype "bidirectional"))
    )
    (net (code "152") (name "unconnected-(G1-PadBOOT0)") (class "Default")
      (node (ref "G1") (pin "BOOT0") (pinfunction "BOOT0_BOOT0") (pintype "bidirectional"))
    )
    (net (code "153") (name "unconnected-(G1-PadIOREF2)") (class "Default")
      (node (ref "G1") (pin "IOREF2") (pinfunction "IOREF2_IOREF2") (pintype "input"))
    )
    (net (code "154") (name "unconnected-(G1-PadNC1-PF7)") (class "Default")
      (node (ref "G1") (pin "NC1-PF7") (pinfunction "NC1-PF7_NC1-PF7") (pintype "bidirectional"))
    )
    (net (code "155") (name "unconnected-(G1-PadNC2-PF6)") (class "Default")
      (node (ref "G1") (pin "NC2-PF6") (pinfunction "NC2-PF6_NC2-PF6") (pintype "bidirectional"))
    )
    (net (code "156") (name "unconnected-(G1-PadNC3)") (class "Default")
      (node (ref "G1") (pin "NC3") (pinfunction "NC3_NC3") (pintype "no_connect"))
    )
    (net (code "157") (name "unconnected-(G1-PadNC4)") (class "Default")
      (node (ref "G1") (pin "NC4") (pinfunction "NC4_NC4") (pintype "no_connect"))
    )
    (net (code "158") (name "unconnected-(G1-PadNC5-PD8)") (class "Default")
      (node (ref "G1") (pin "NC5-PD8") (pinfunction "NC5-PD8_NC5-PD8") (pintype "bidirectional"))
    )
    (net (code "159") (name "unconnected-(G1-PadNC6-PB11)") (class "Default")
      (node (ref "G1") (pin "NC6-PB11") (pinfunction "NC6-PB11_NC6-PB11") (pintype "no_connect"))
    )
    (net (code "160") (name "unconnected-(G1-PadNC7-PF5)") (class "Default")
      (node (ref "G1") (pin "NC7-PF5") (pinfunction "NC7-PF5_NC7-PF5") (pintype "bidirectional"))
    )
    (net (code "161") (name "unconnected-(G1-PadNC8-PF4)") (class "Default")
      (node (ref "G1") (pin "NC8-PF4") (pinfunction "NC8-PF4_NC8-PF4") (pintype "bidirectional"))
    )
    (net (code "162") (name "unconnected-(G1-PadNRESET)") (class "Default")
      (node (ref "G1") (pin "NRESET") (pinfunction "NRESET_NRESET") (pintype "input"))
    )
    (net (code "163") (name "unconnected-(G1-PadPA1)") (class "Default")
      (node (ref "G1") (pin "PA1") (pinfunction "PA1_PA1") (pintype "bidirectional"))
    )
    (net (code "164") (name "unconnected-(G1-PadPA2)") (class "Default")
      (node (ref "G1") (pin "PA2") (pinfunction "PA2_PA2") (pintype "bidirectional"))
    )
    (net (code "165") (name "unconnected-(G1-PadPA3)") (class "Default")
      (node (ref "G1") (pin "PA3") (pinfunction "PA3_PA3") (pintype "bidirectional"))
    )
    (net (code "166") (name "unconnected-(G1-PadPA5)") (class "Default")
      (node (ref "G1") (pin "PA5") (pinfunction "PA5_PA5") (pintype "bidirectional"))
    )
    (net (code "167") (name "unconnected-(G1-PadPA7)") (class "Default")
      (node (ref "G1") (pin "PA7") (pinfunction "PA7_PA7") (pintype "bidirectional"))
    )
    (net (code "168") (name "unconnected-(G1-PadPA9)") (class "Default")
      (node (ref "G1") (pin "PA9") (pinfunction "PA9_PA9") (pintype "bidirectional"))
    )
    (net (code "169") (name "unconnected-(G1-PadPA10)") (class "Default")
      (node (ref "G1") (pin "PA10") (pinfunction "PA10_PA10") (pintype "bidirectional"))
    )
    (net (code "170") (name "unconnected-(G1-PadPA11)") (class "Default")
      (node (ref "G1") (pin "PA11") (pinfunction "PA11_PA11") (pintype "bidirectional"))
    )
    (net (code "171") (name "unconnected-(G1-PadPA12)") (class "Default")
      (node (ref "G1") (pin "PA12") (pinfunction "PA12_PA12") (pintype "bidirectional"))
    )
    (net (code "172") (name "unconnected-(G1-PadPA13)") (class "Default")
      (node (ref "G1") (pin "PA13") (pinfunction "PA13_PA13") (pintype "bidirectional"))
    )
    (net (code "173") (name "unconnected-(G1-PadPA14)") (class "Default")
      (node (ref "G1") (pin "PA14") (pinfunction "PA14_PA14") (pintype "bidirectional"))
    )
    (net (code "174") (name "unconnected-(G1-PadPB0)") (class "Default")
      (node (ref "G1") (pin "PB0") (pinfunction "PB0_PB0") (pintype "bidirectional"))
    )
    (net (code "175") (name "unconnected-(G1-PadPC1)") (class "Default")
      (node (ref "G1") (pin "PC1") (pinfunction "PC1_PC1") (pintype "bidirectional"))
    )
    (net (code "176") (name "unconnected-(G1-PadPC4)") (class "Default")
      (node (ref "G1") (pin "PC4") (pinfunction "PC4_PC4") (pintype "bidirectional"))
    )
    (net (code "177") (name "unconnected-(G1-PadPC5)") (class "Default")
      (node (ref "G1") (pin "PC5") (pinfunction "PC5_PC5") (pintype "bidirectional"))
    )
    (net (code "178") (name "unconnected-(G1-PadPC13)") (class "Default")
      (node (ref "G1") (pin "PC13") (pinfunction "PC13_PC13") (pintype "bidirectional"))
    )
    (net (code "179") (name "unconnected-(G1-PadPC14)") (class "Default")
      (node (ref "G1") (pin "PC14") (pinfunction "PC14_PC14") (pintype "bidirectional"))
    )
    (net (code "180") (name "unconnected-(G1-PadPC15)") (class "Default")
      (node (ref "G1") (pin "PC15") (pinfunction "PC15_PC15") (pintype "bidirectional"))
    )
    (net (code "181") (name "unconnected-(G1-PadPF0-PH0)") (class "Default")
      (node (ref "G1") (pin "PF0-PH0") (pinfunction "PF0-PH0_PF0-PH0") (pintype "bidirectional"))
    )
    (net (code "182") (name "unconnected-(H1-MOUNT-PadB3,3)") (class "Default")
      (node (ref "H1") (pin "B3,3") (pinfunction "MOUNT_B3,3") (pintype "passive"))
    )
    (net (code "183") (name "unconnected-(H2-MOUNT-PadB3,3)") (class "Default")
      (node (ref "H2") (pin "B3,3") (pinfunction "MOUNT_B3,3") (pintype "passive"))
    )
    (net (code "184") (name "unconnected-(H3-MOUNT-PadB3,3)") (class "Default")
      (node (ref "H3") (pin "B3,3") (pinfunction "MOUNT_B3,3") (pintype "passive"))
    )
    (net (code "185") (name "unconnected-(H4-MOUNT-PadB3,3)") (class "Default")
      (node (ref "H4") (pin "B3,3") (pinfunction "MOUNT_B3,3") (pintype "passive"))
    )
  )
)
